# Synthesizer.net
KiCad netlist of a schematic drawn in Altium Designer
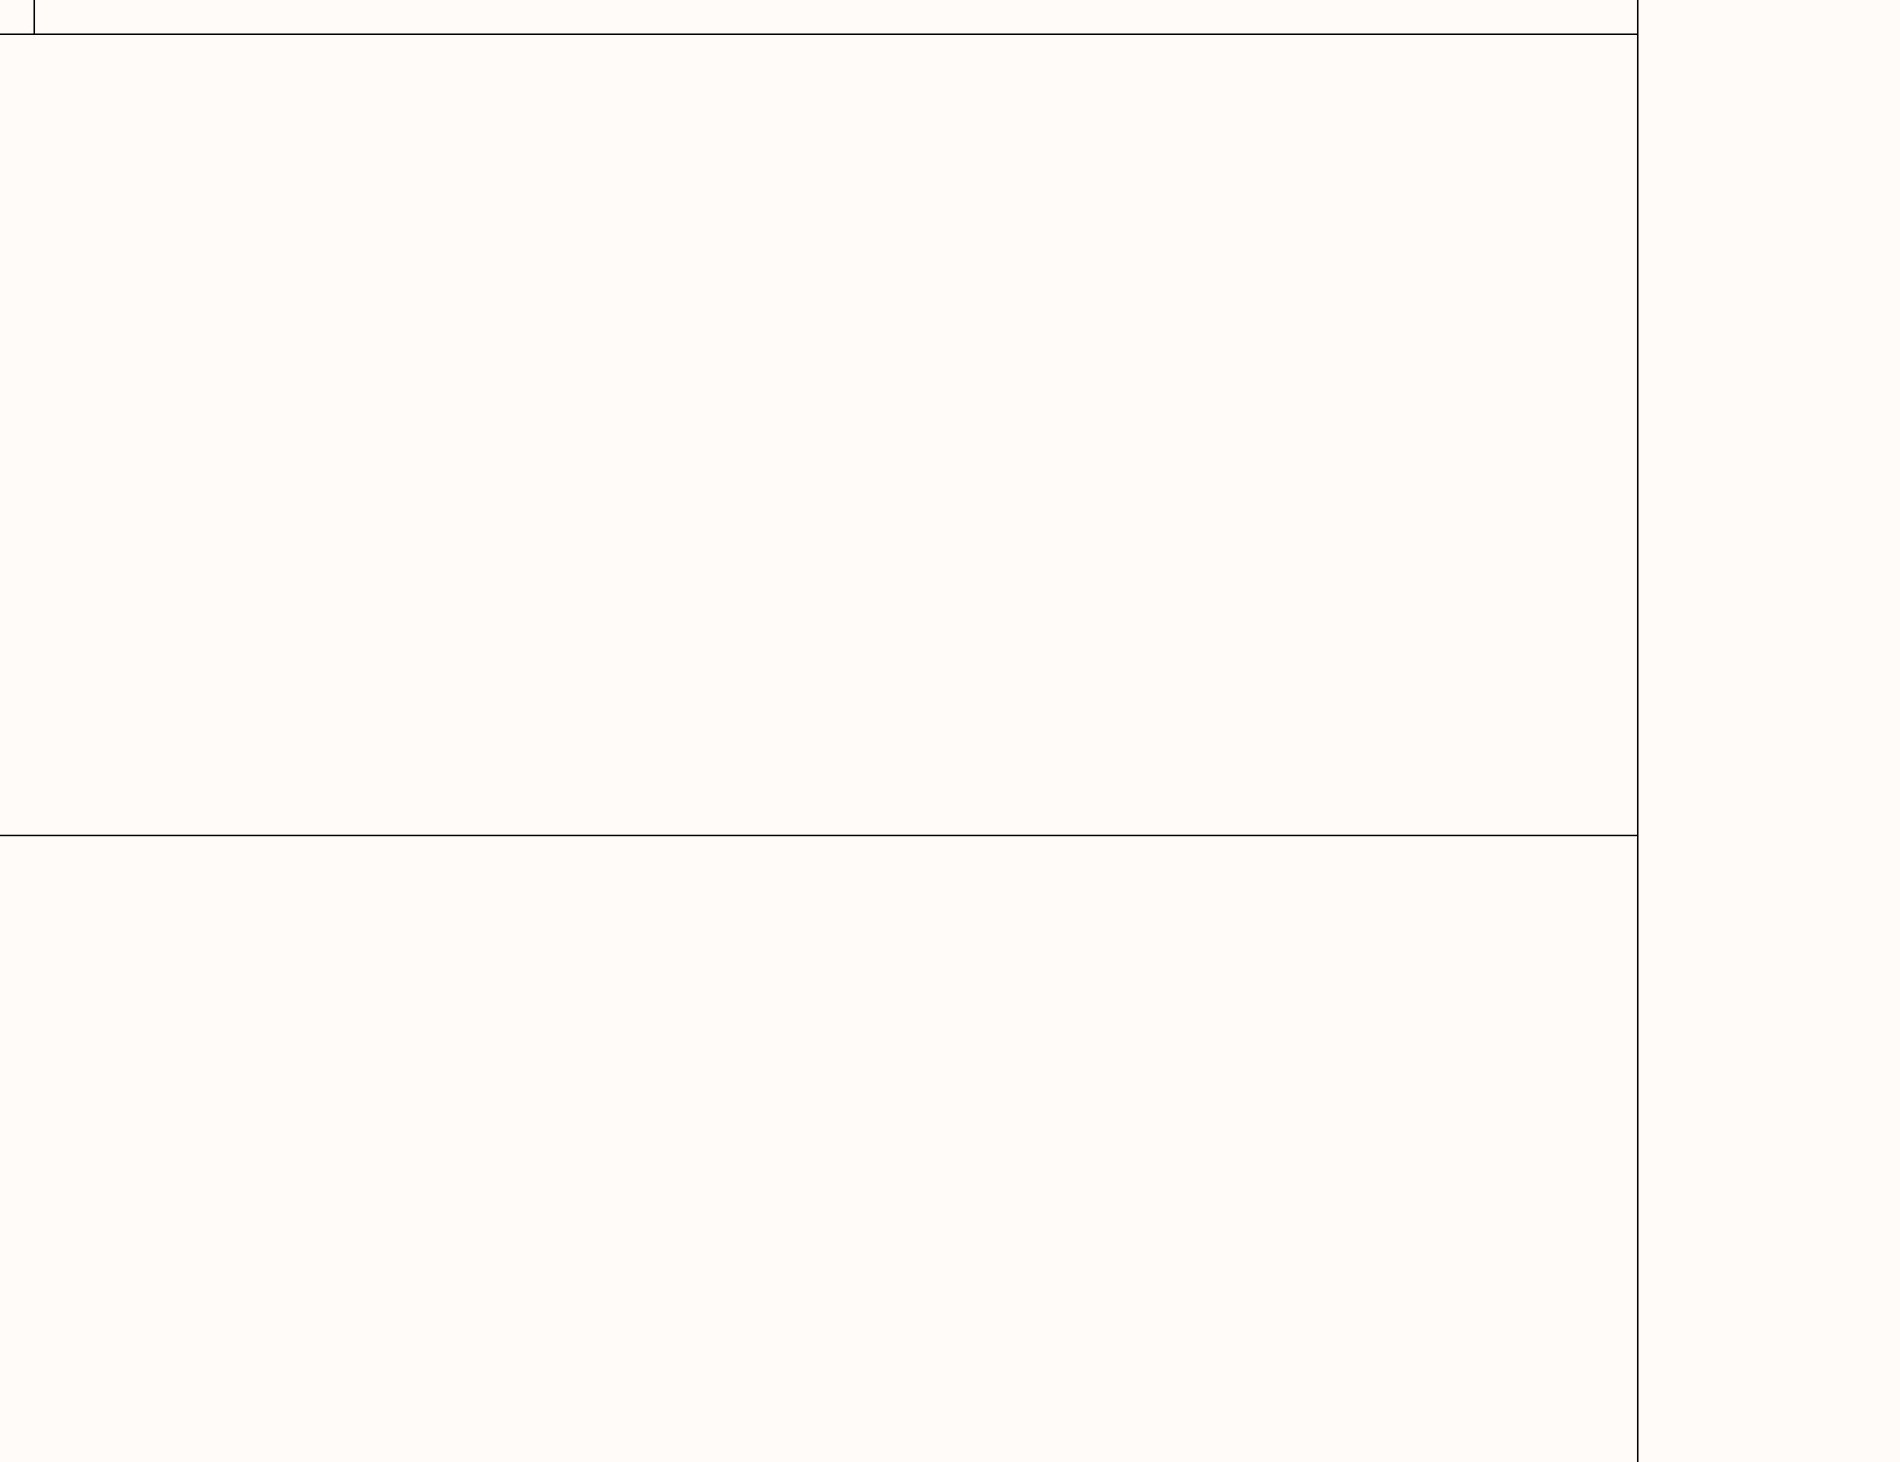
[diagram p0: Synthesizer.SchDoc, top column 1 of 4]
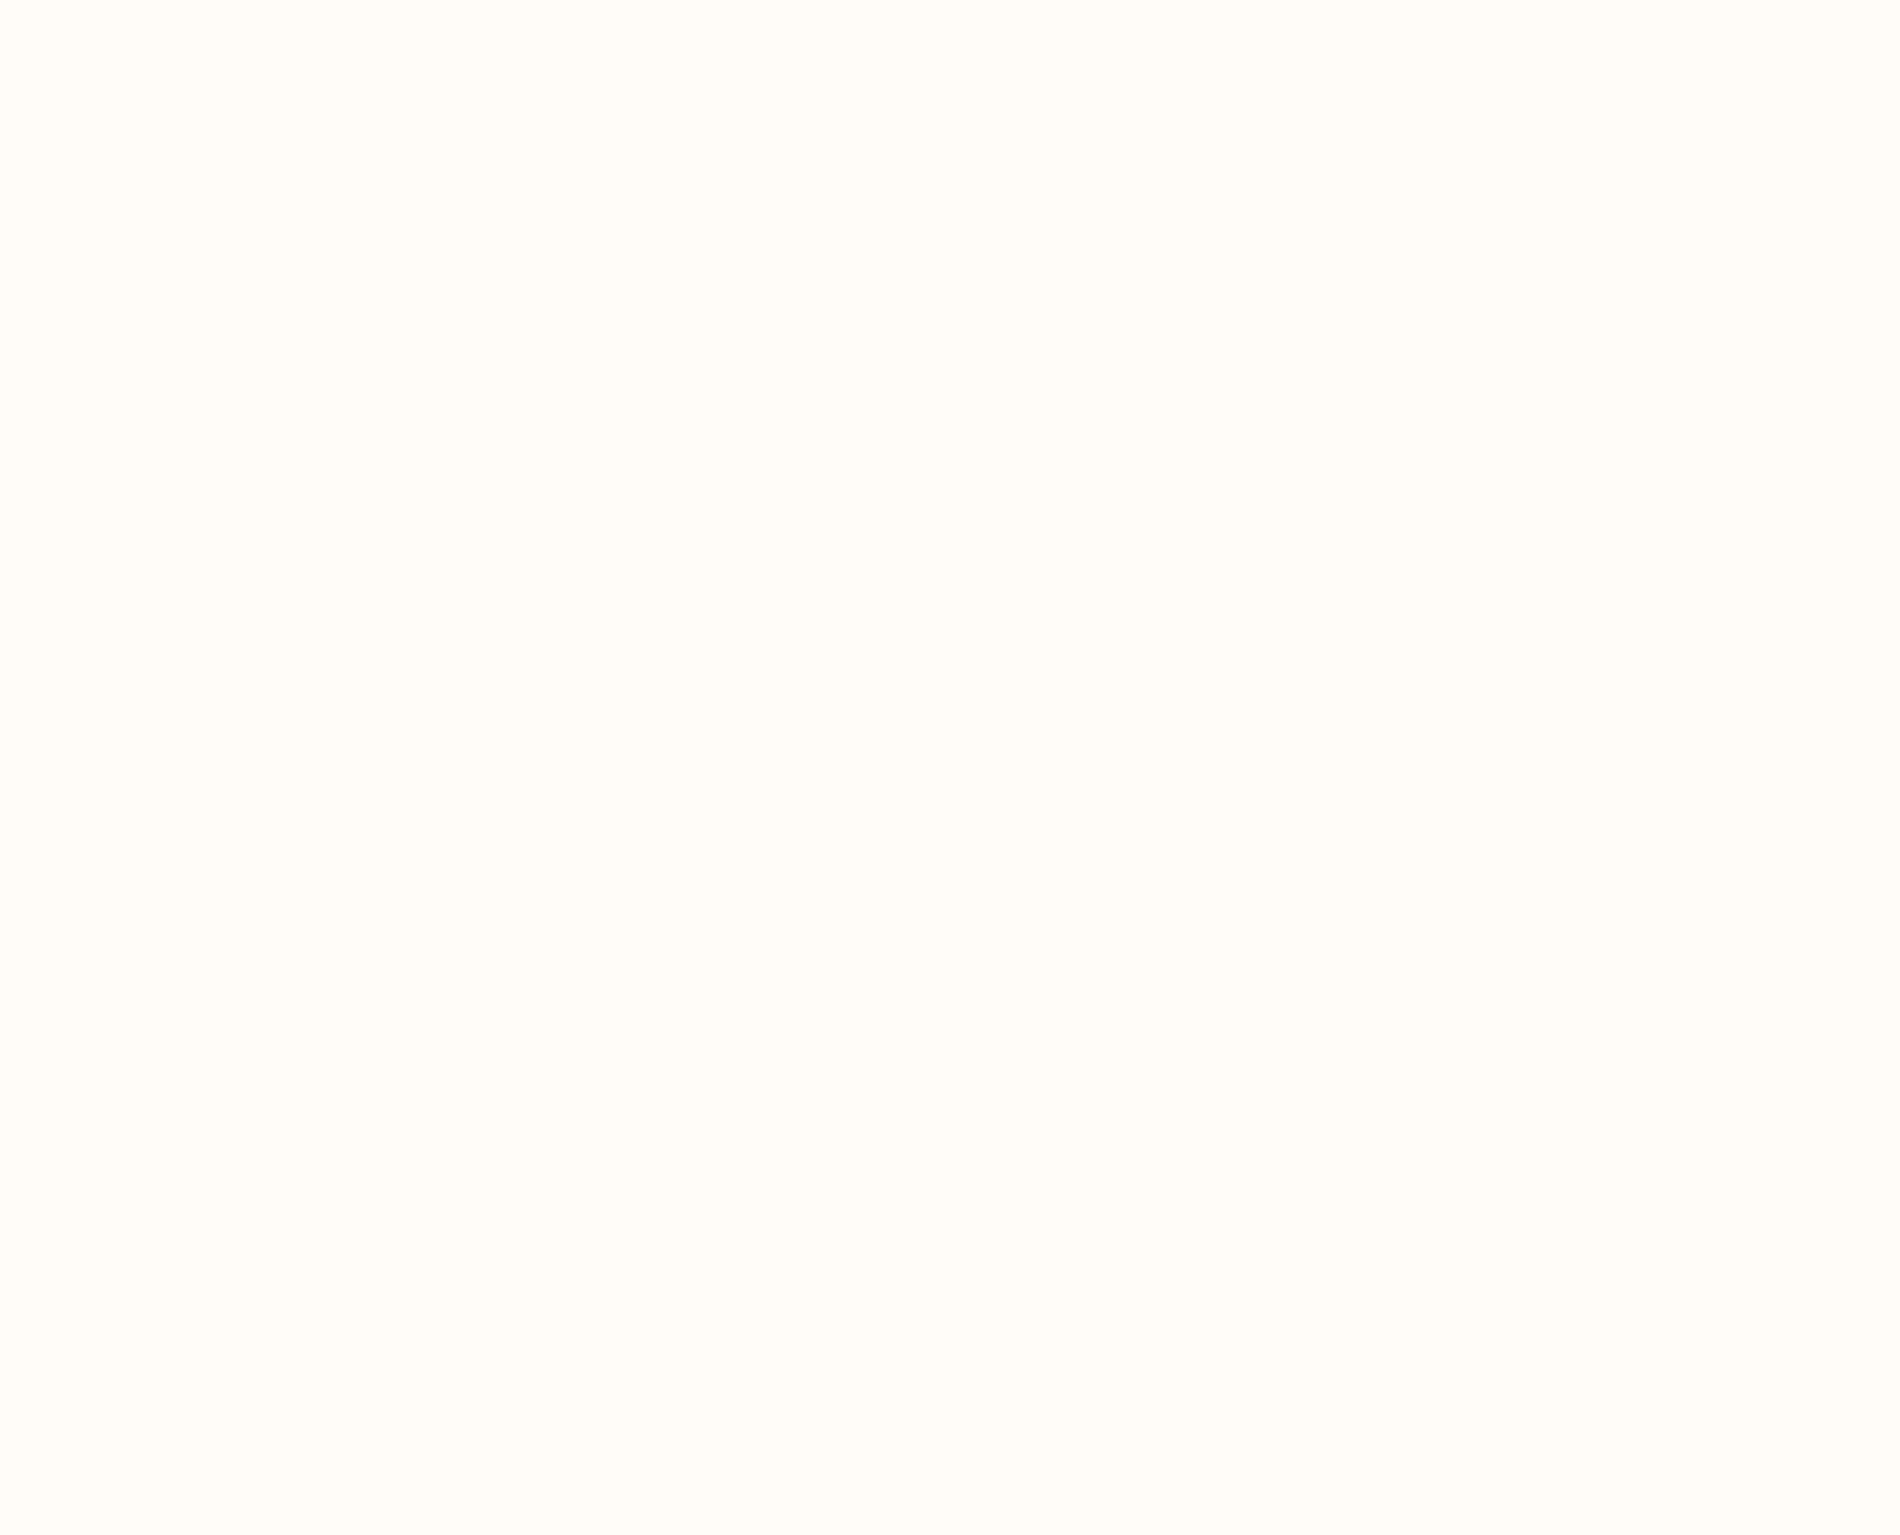
[diagram p1: Synthesizer.SchDoc, top column 2 of 4]
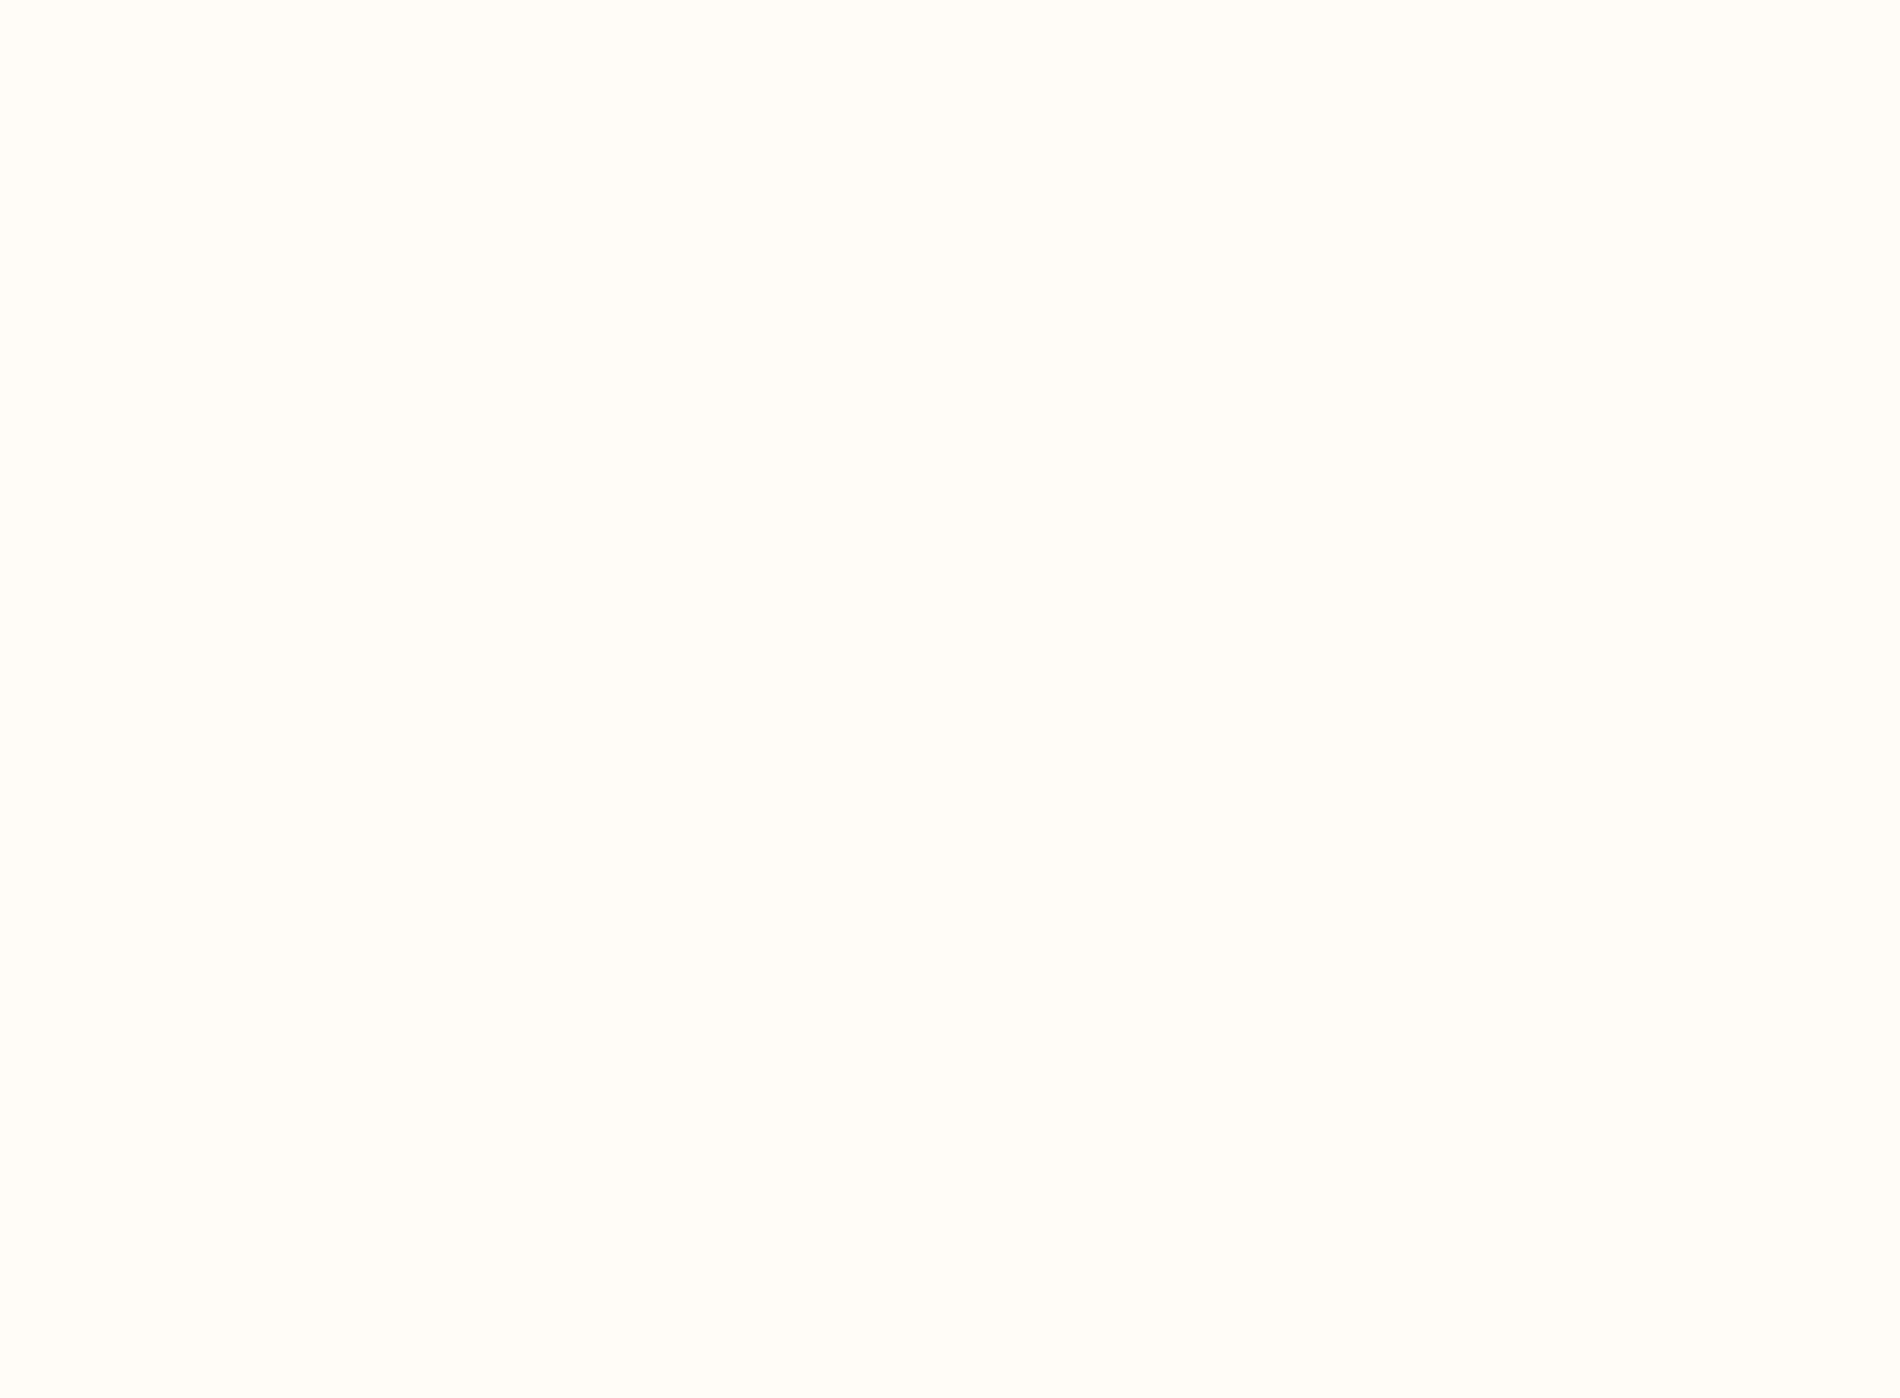
[diagram p2: Synthesizer.SchDoc, top column 3 of 4]
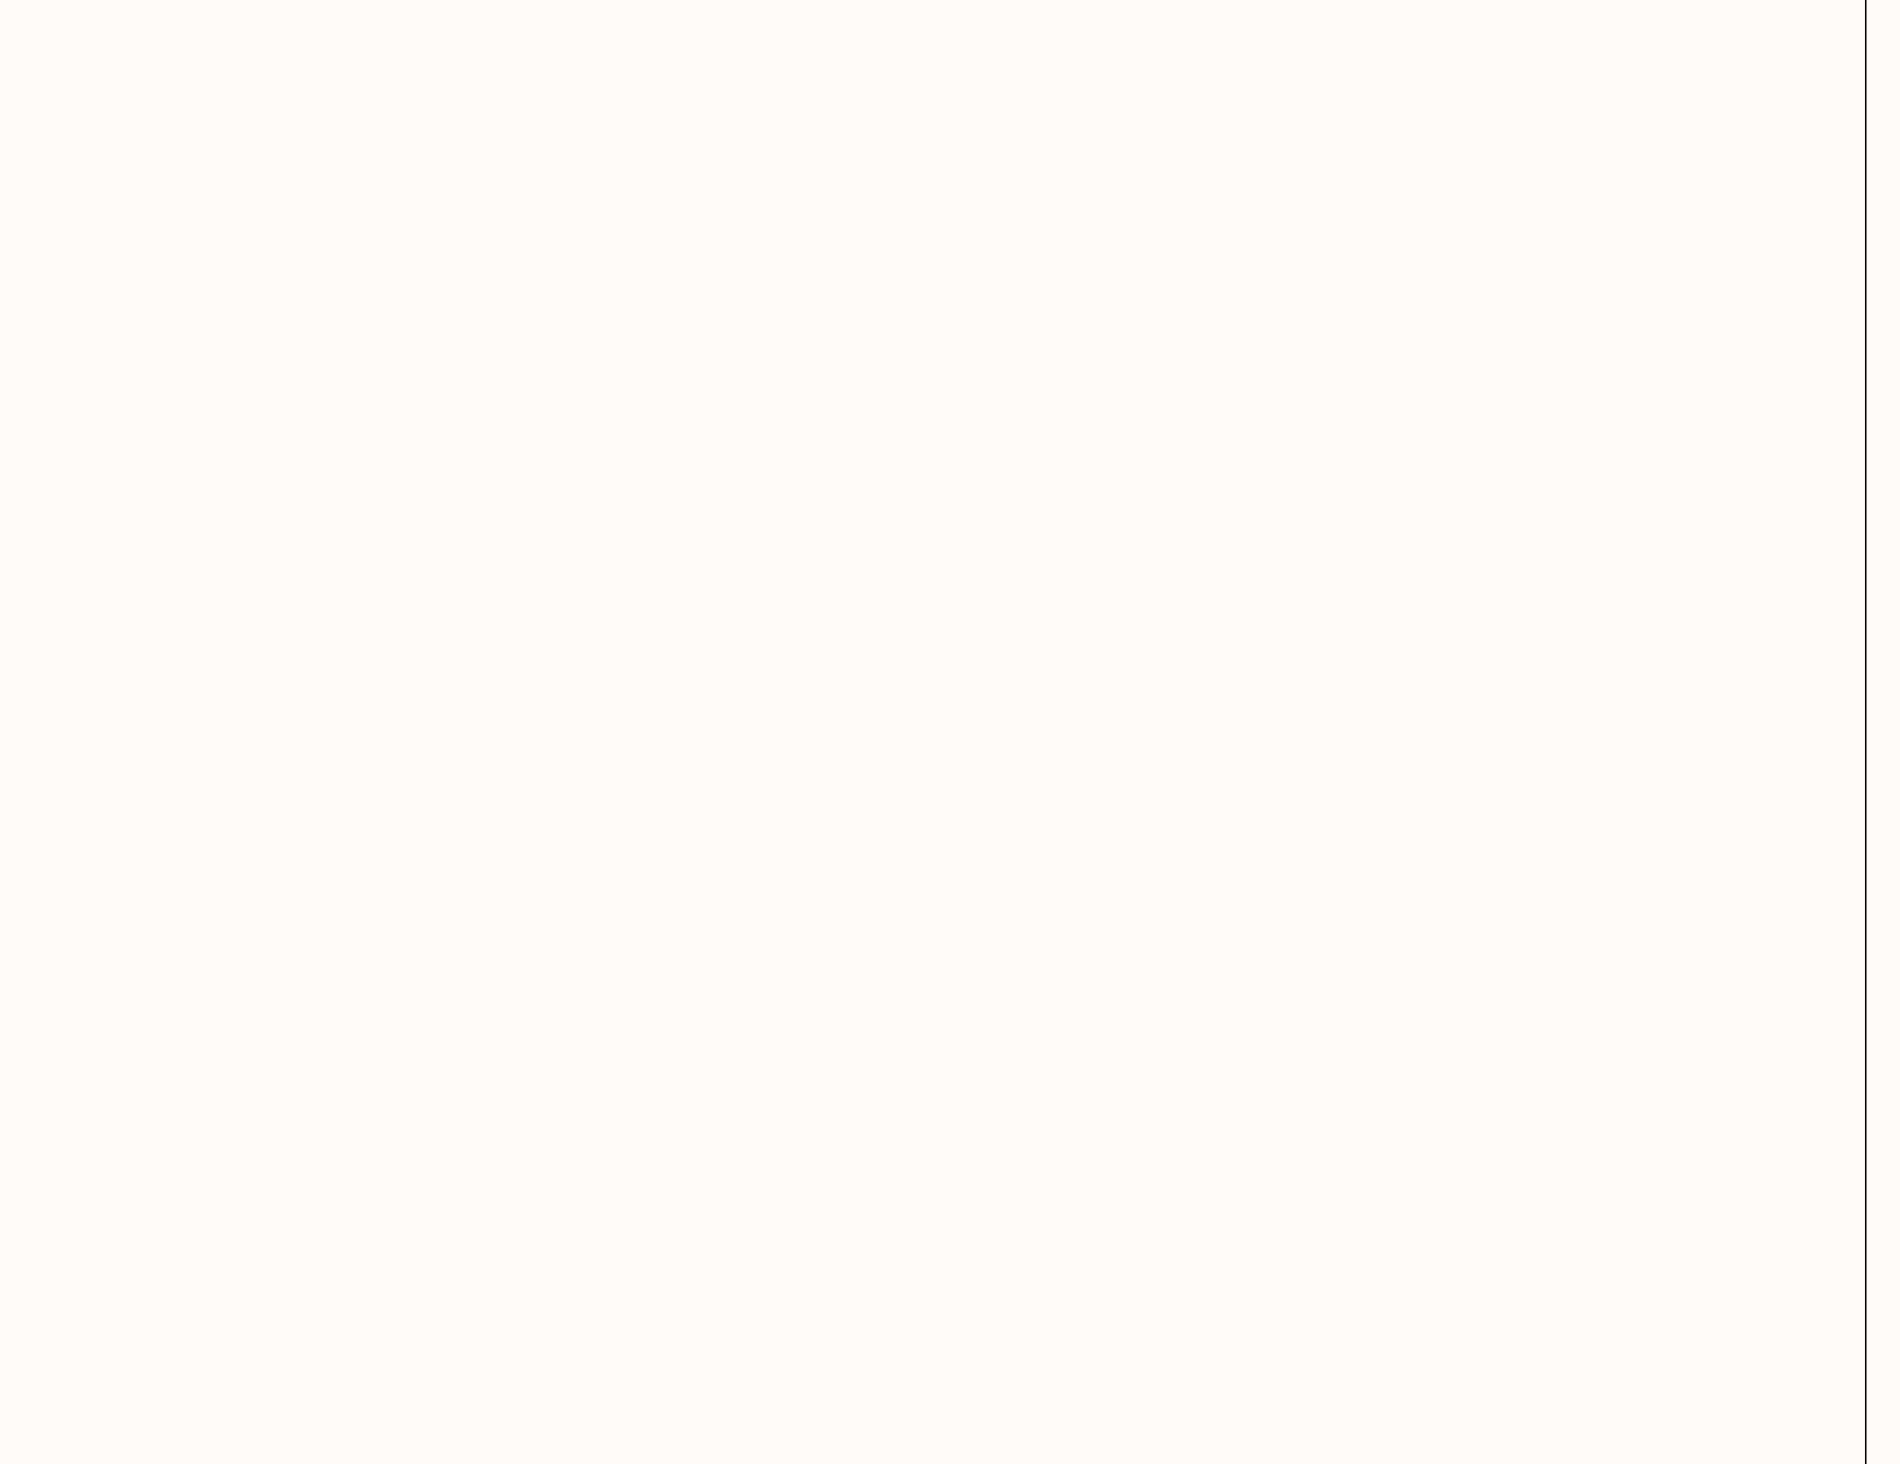
[diagram p3: Synthesizer.SchDoc, top column 4 of 4]
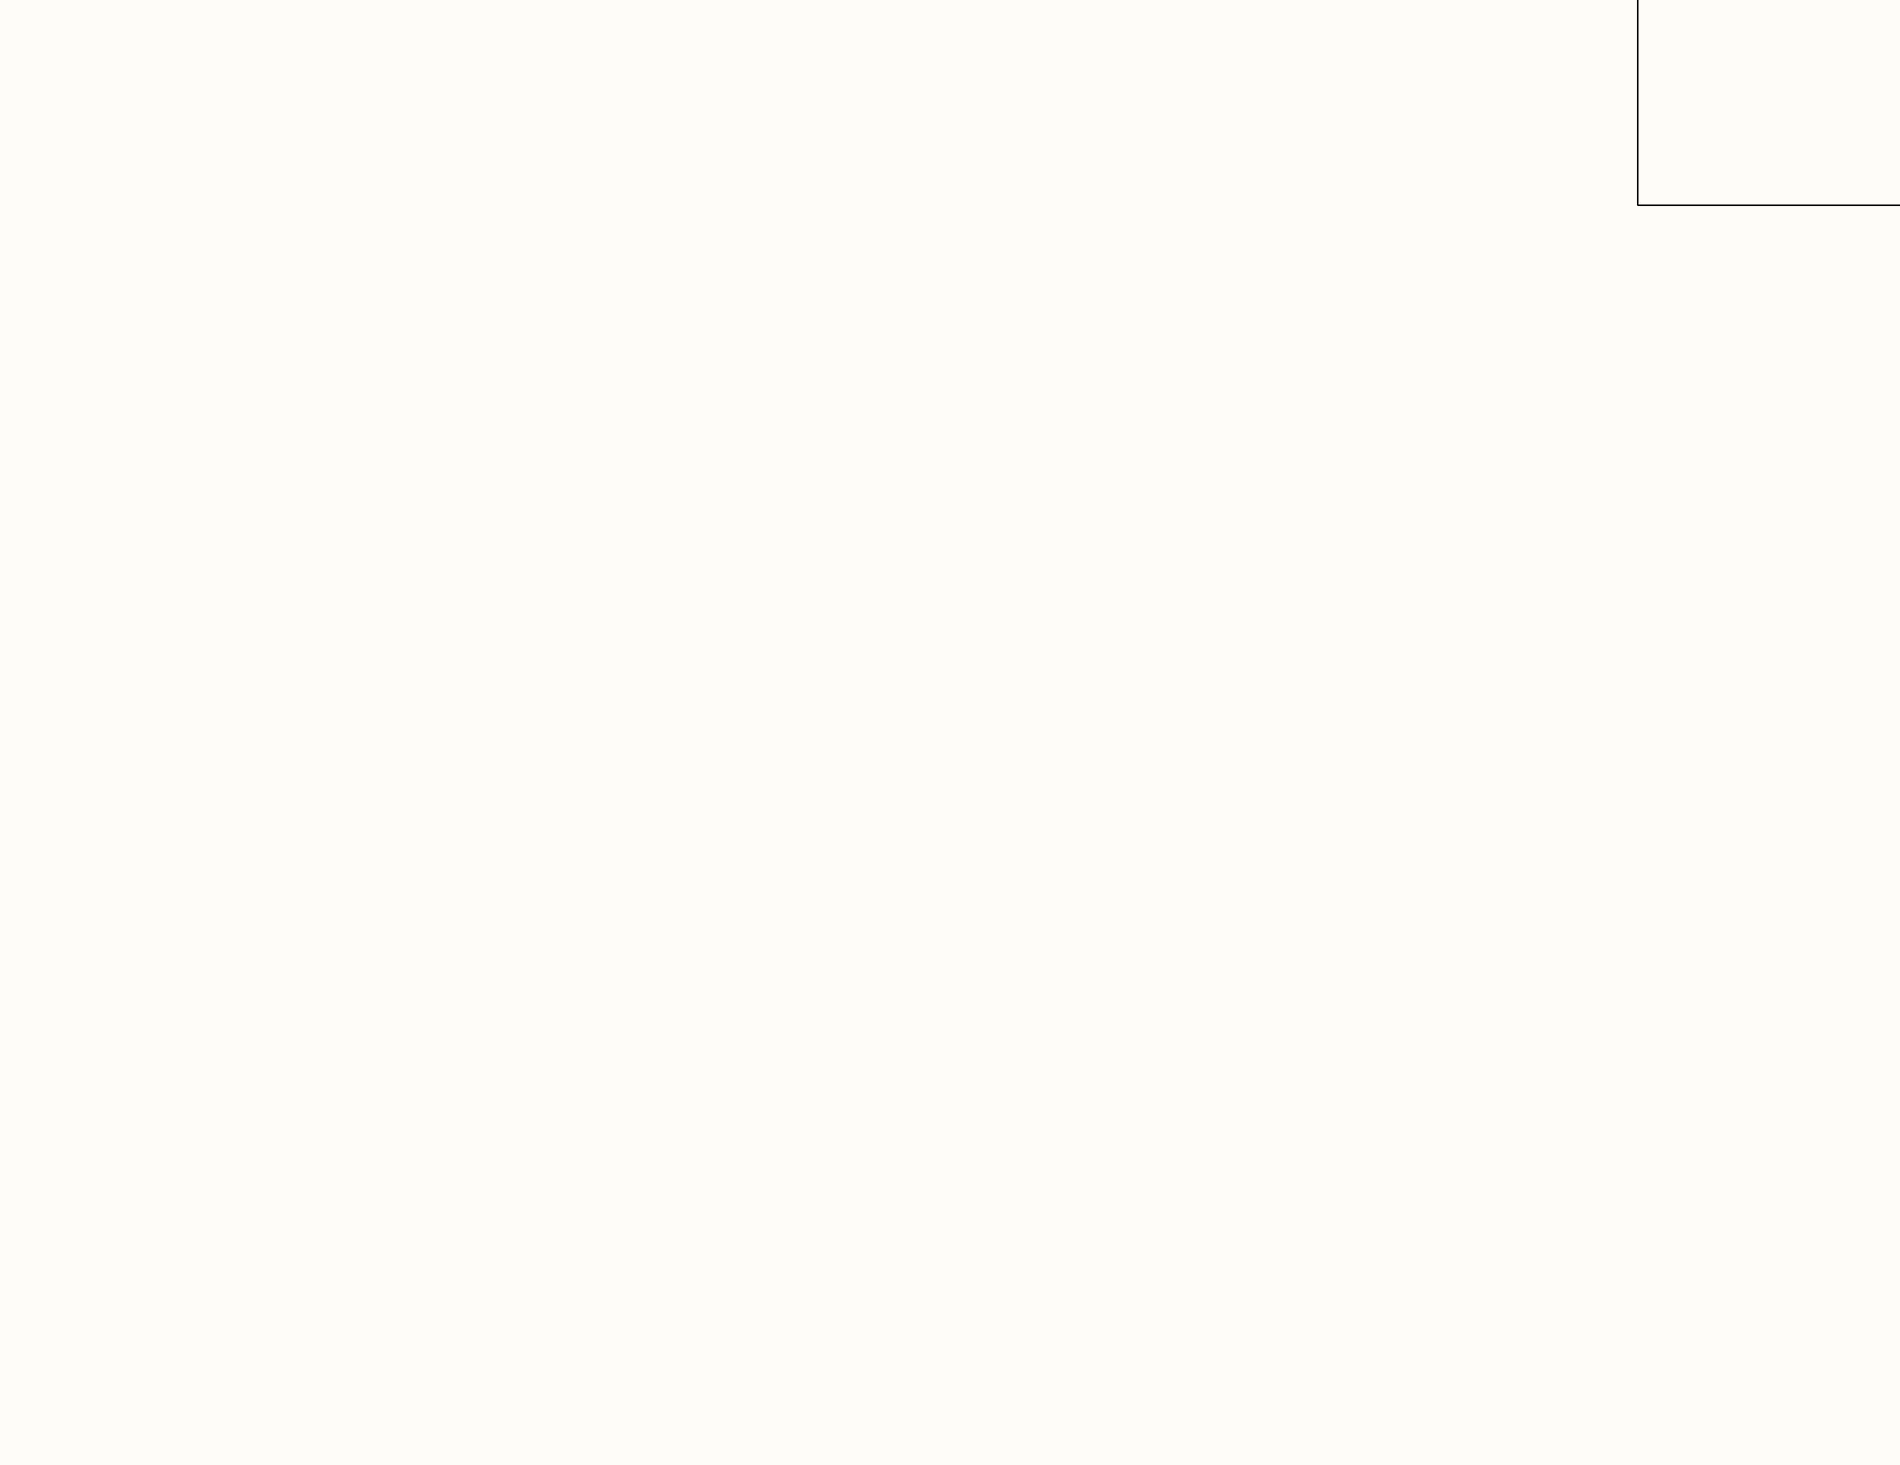
[diagram p4: Synthesizer.SchDoc, centre column 1 of 4]
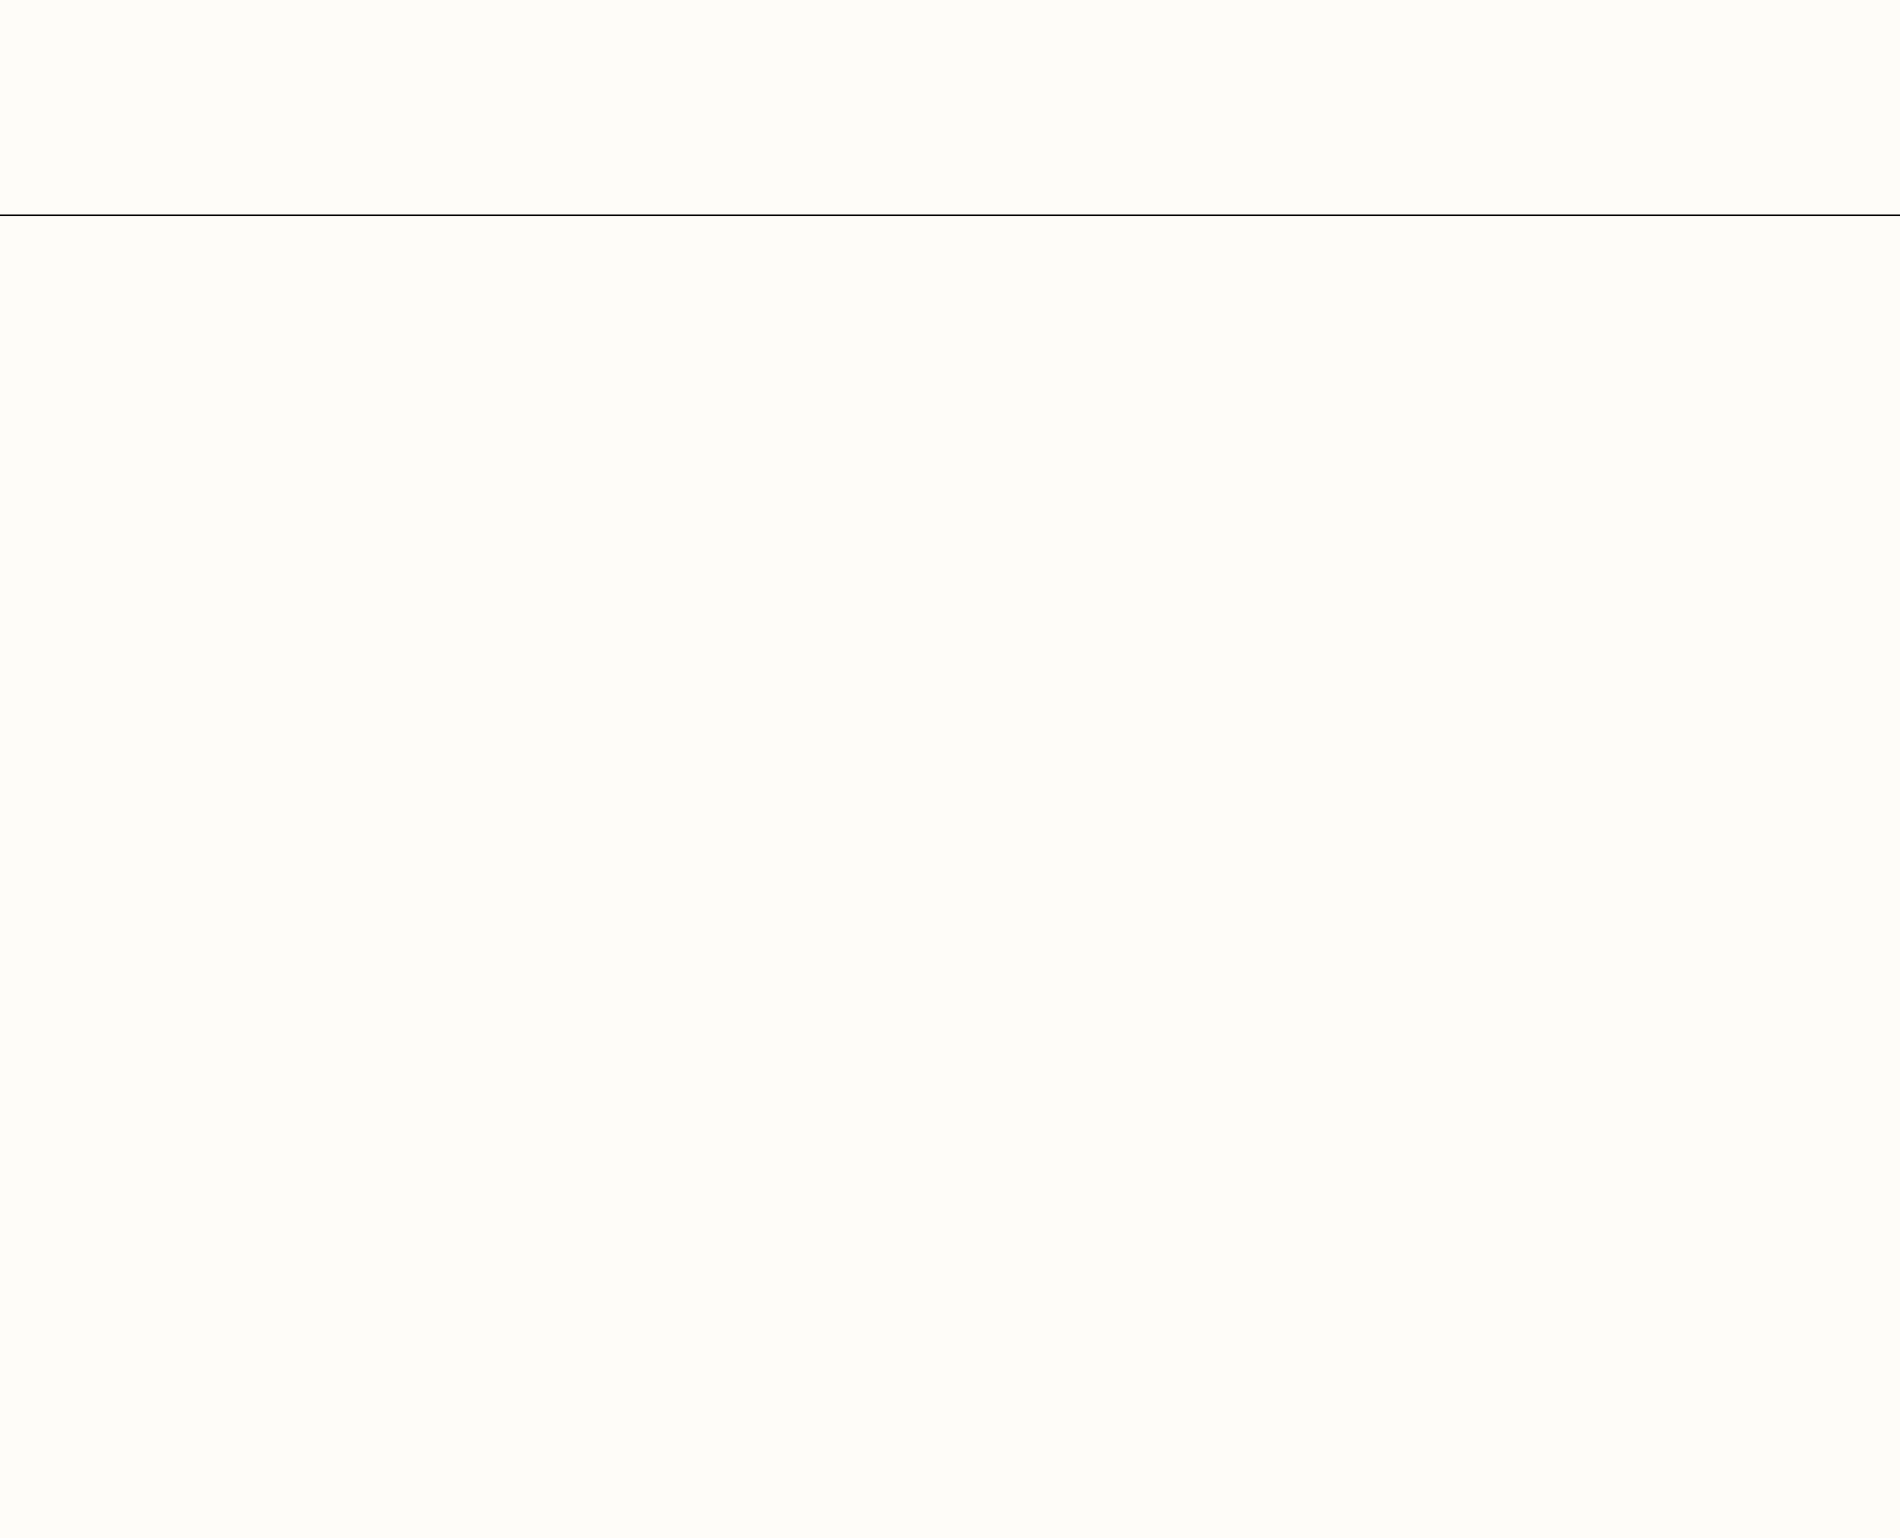
[diagram p5: Synthesizer.SchDoc, centre column 2 of 4]
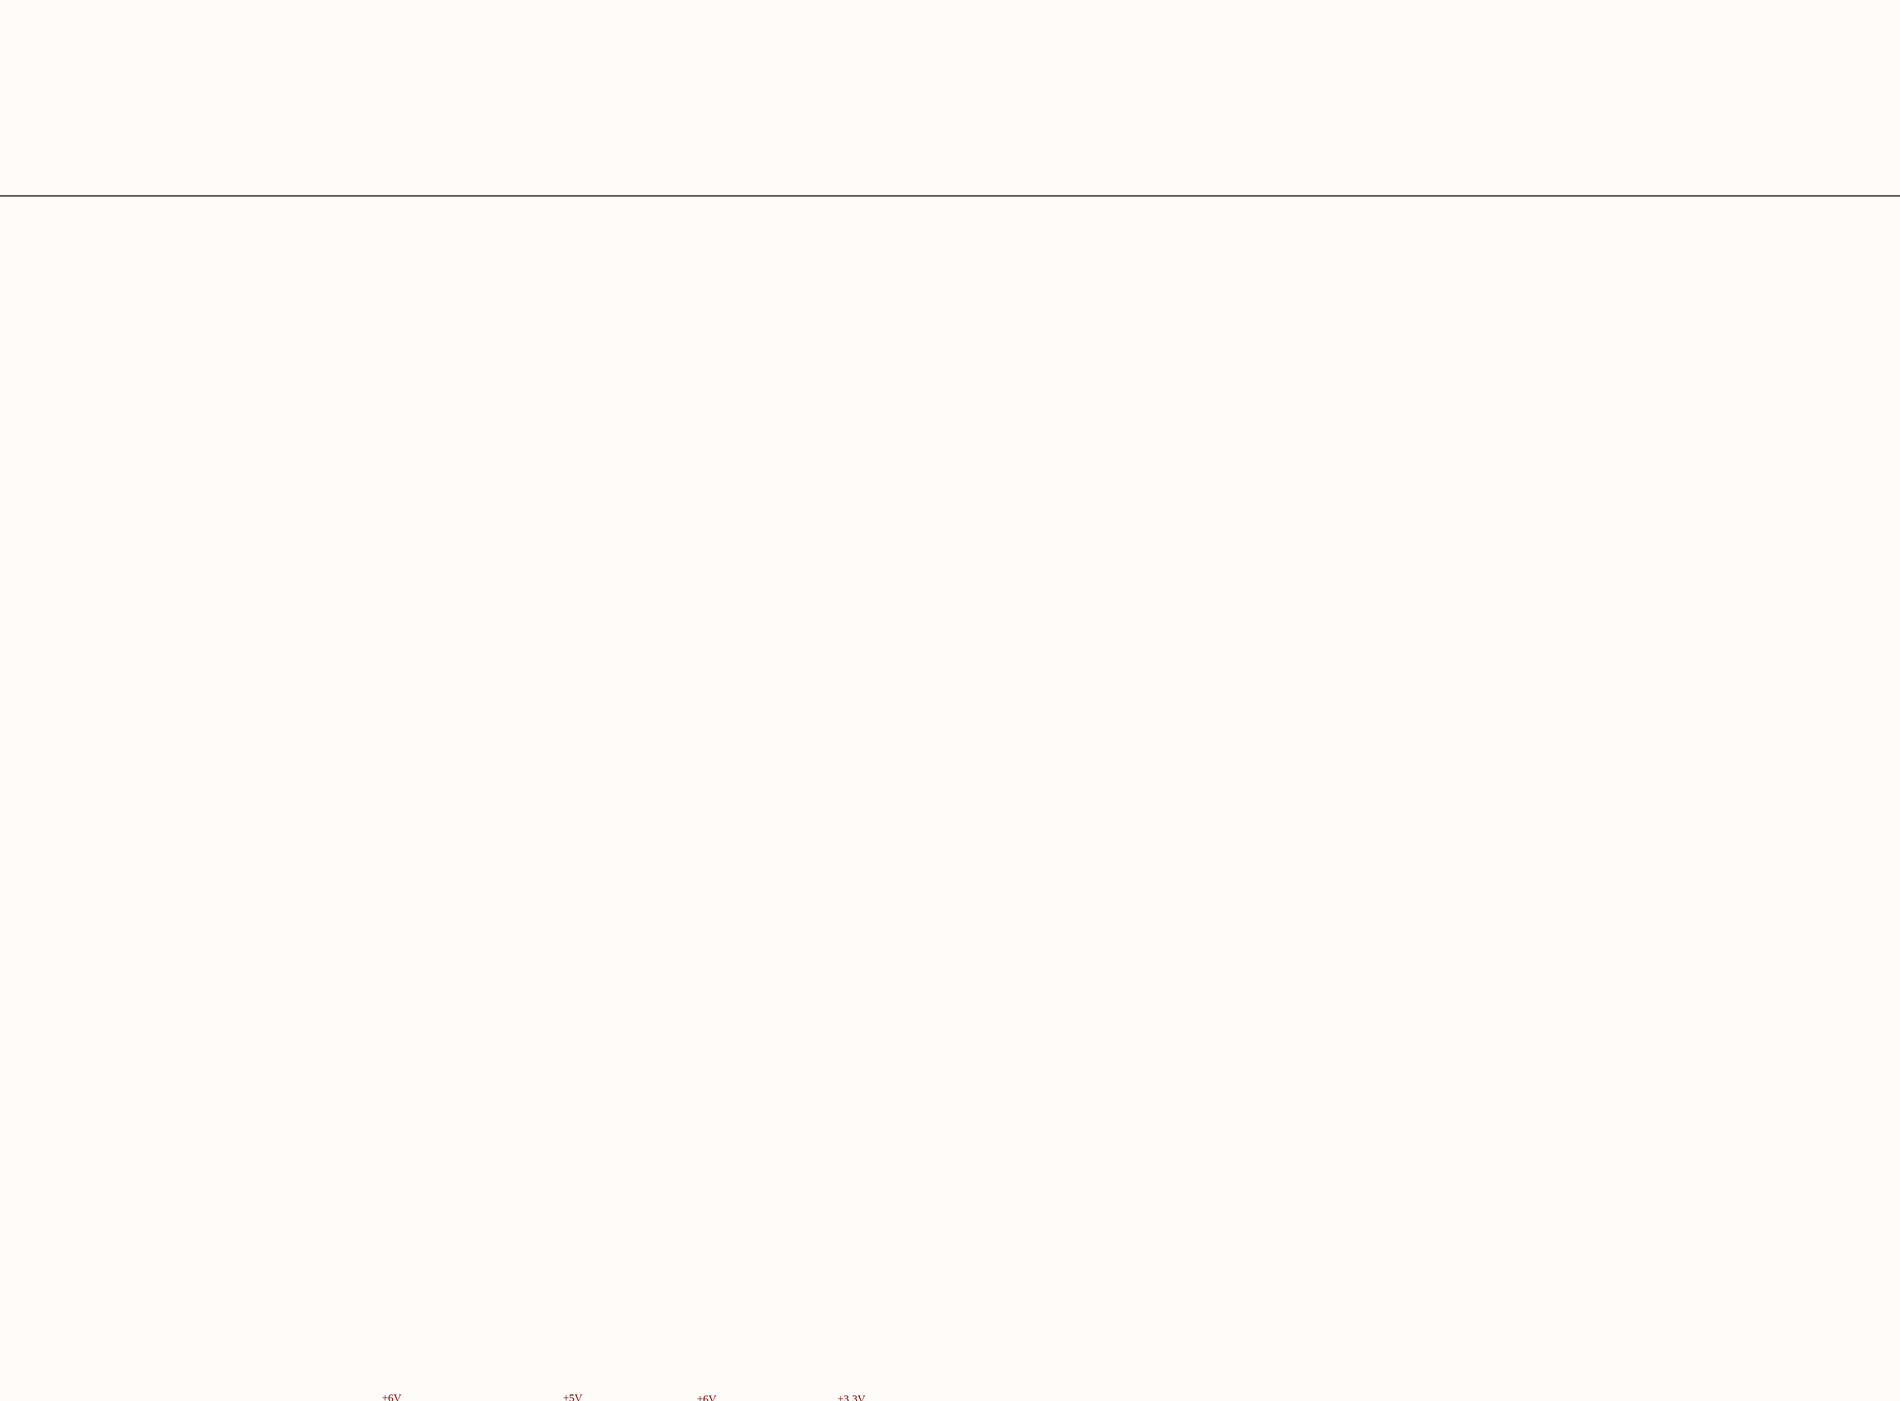
[diagram p6: Synthesizer.SchDoc, centre column 3 of 4]
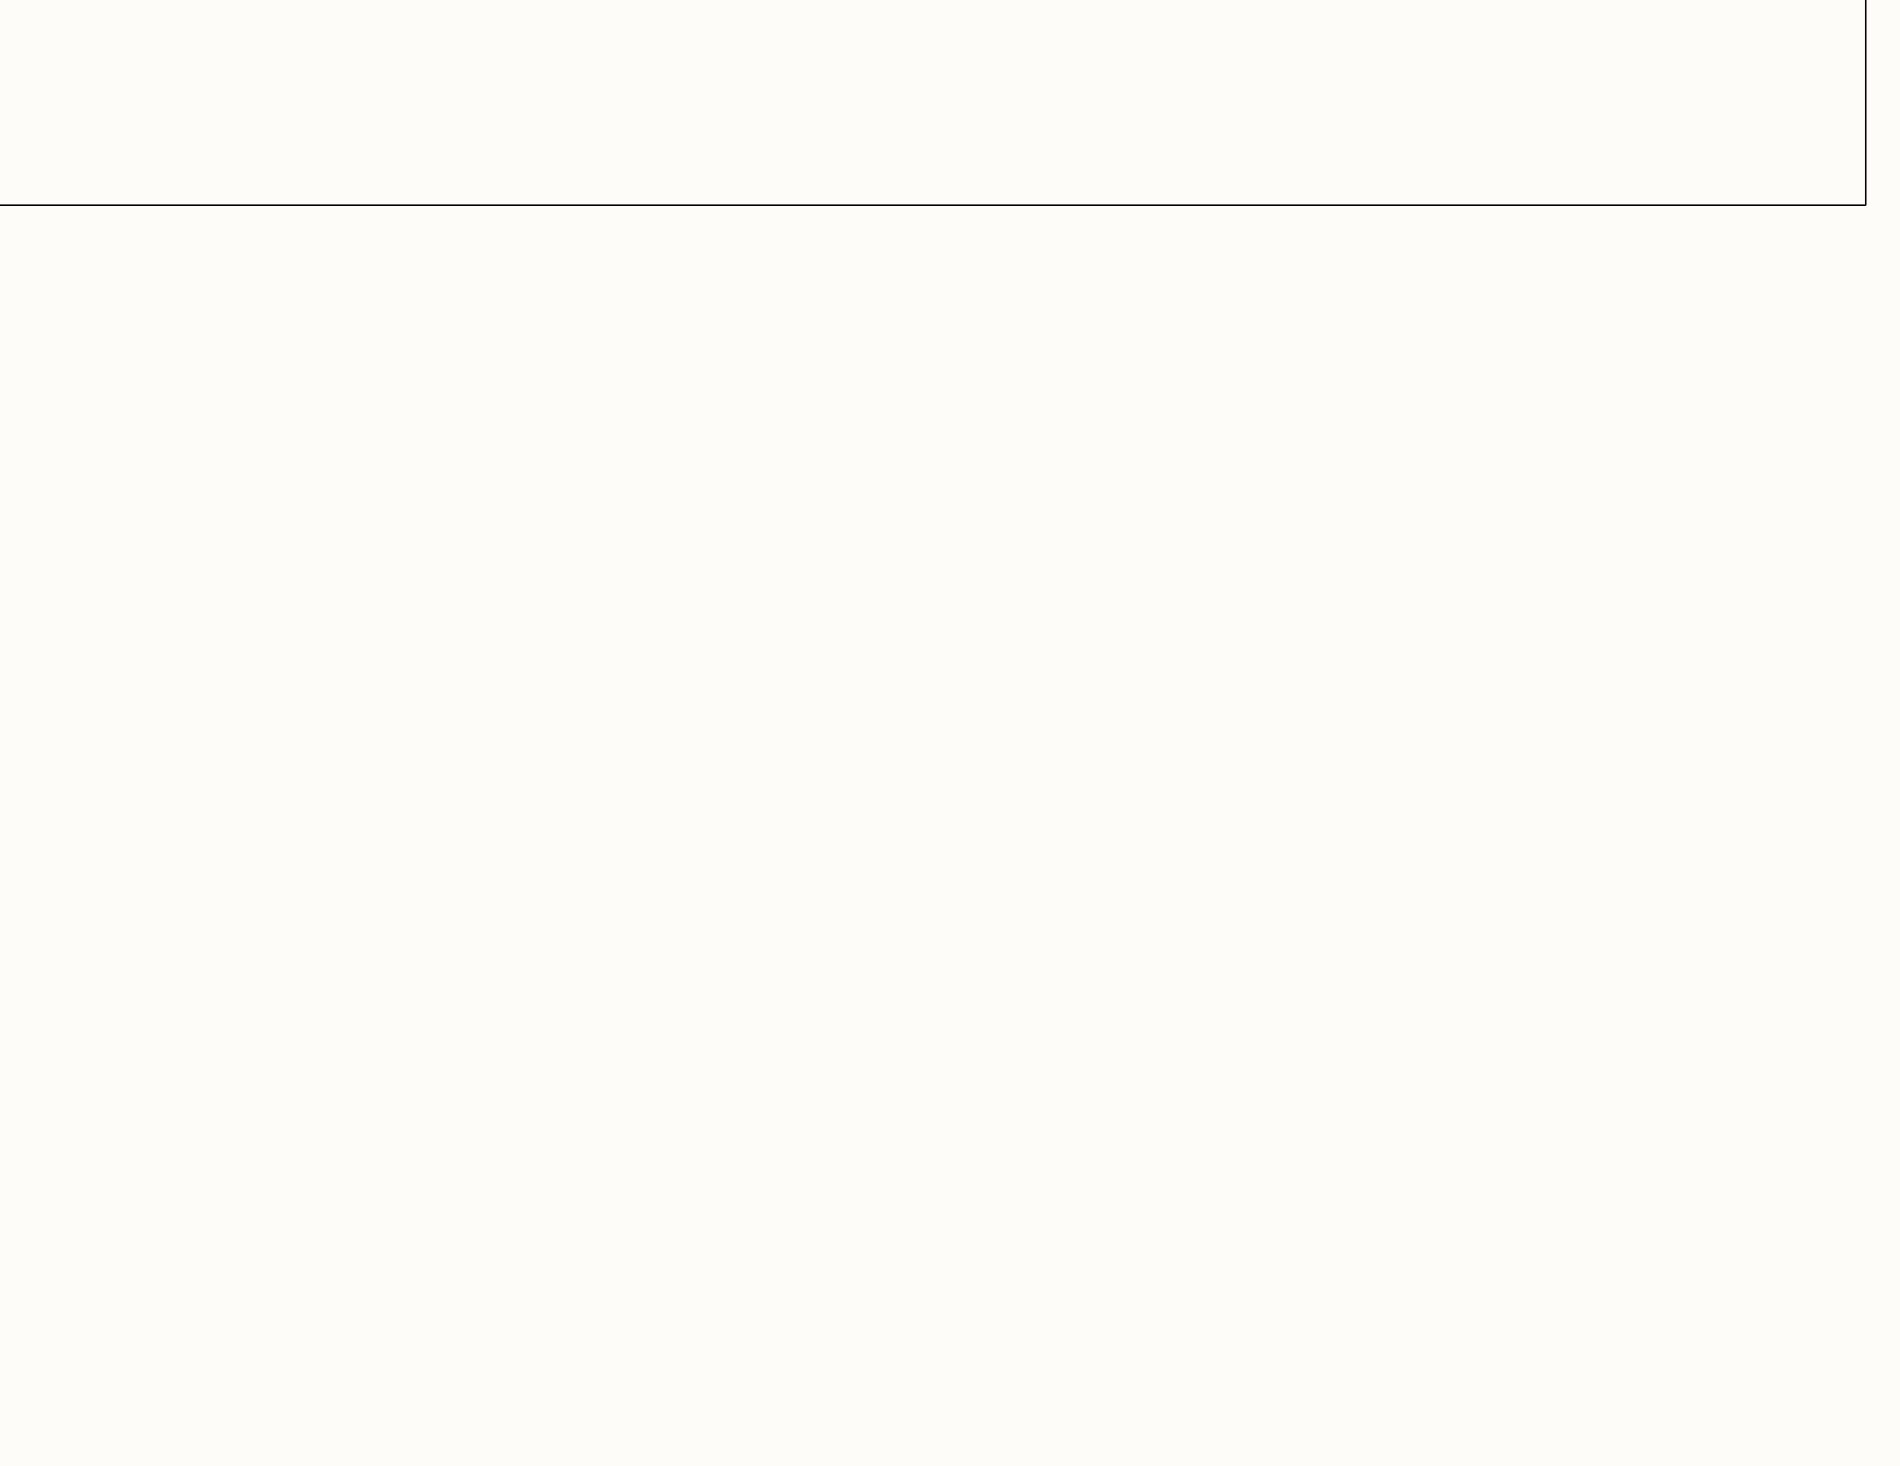
[diagram p7: Synthesizer.SchDoc, centre column 4 of 4]
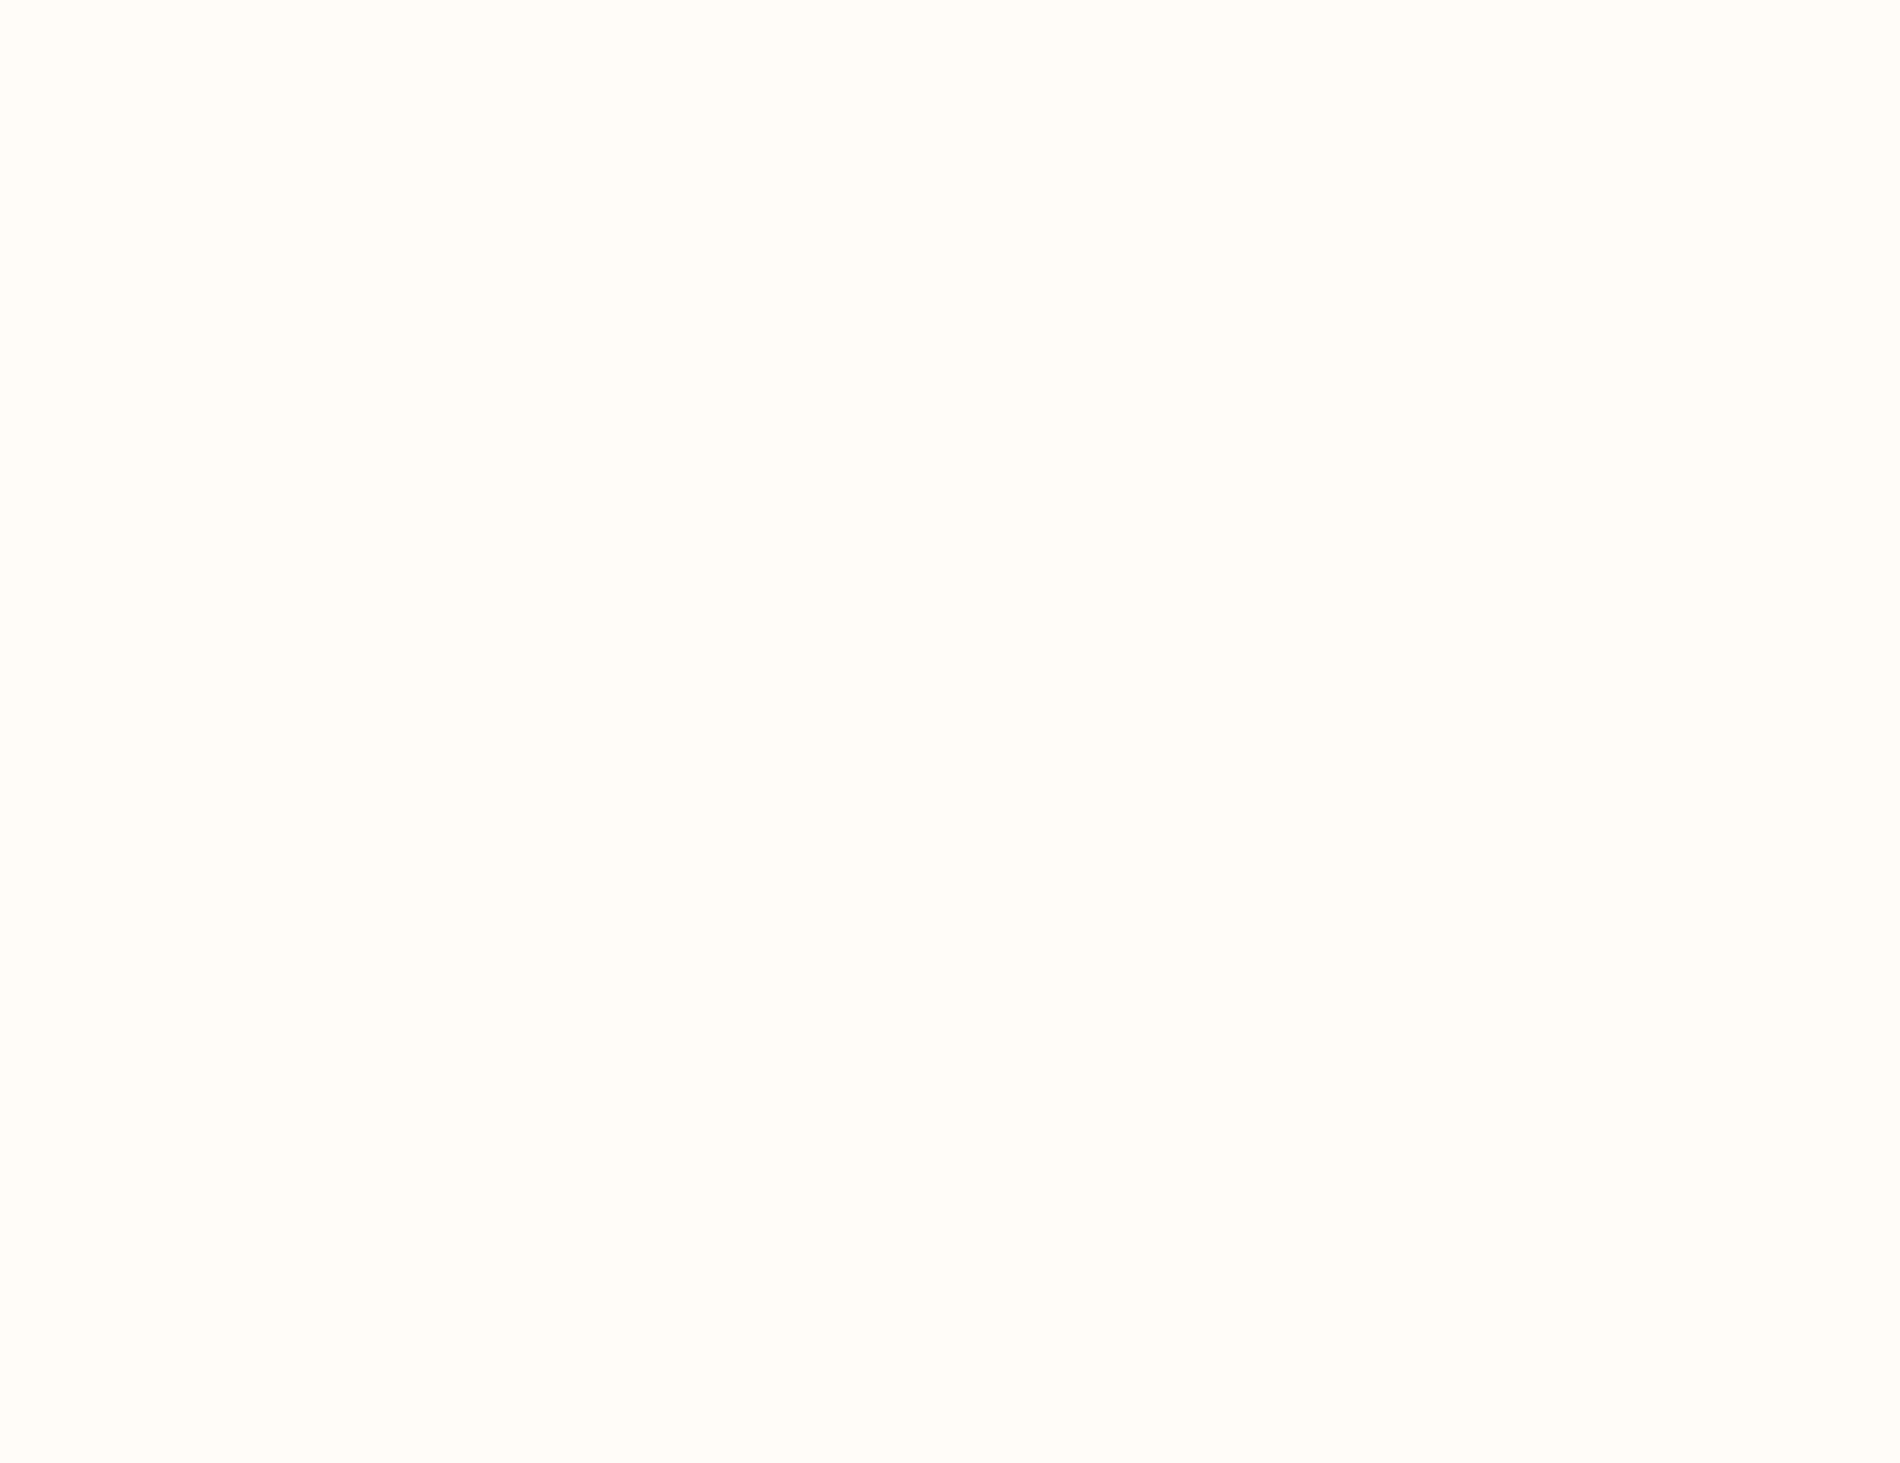
[diagram p8: Synthesizer.SchDoc, bottom column 1 of 4]
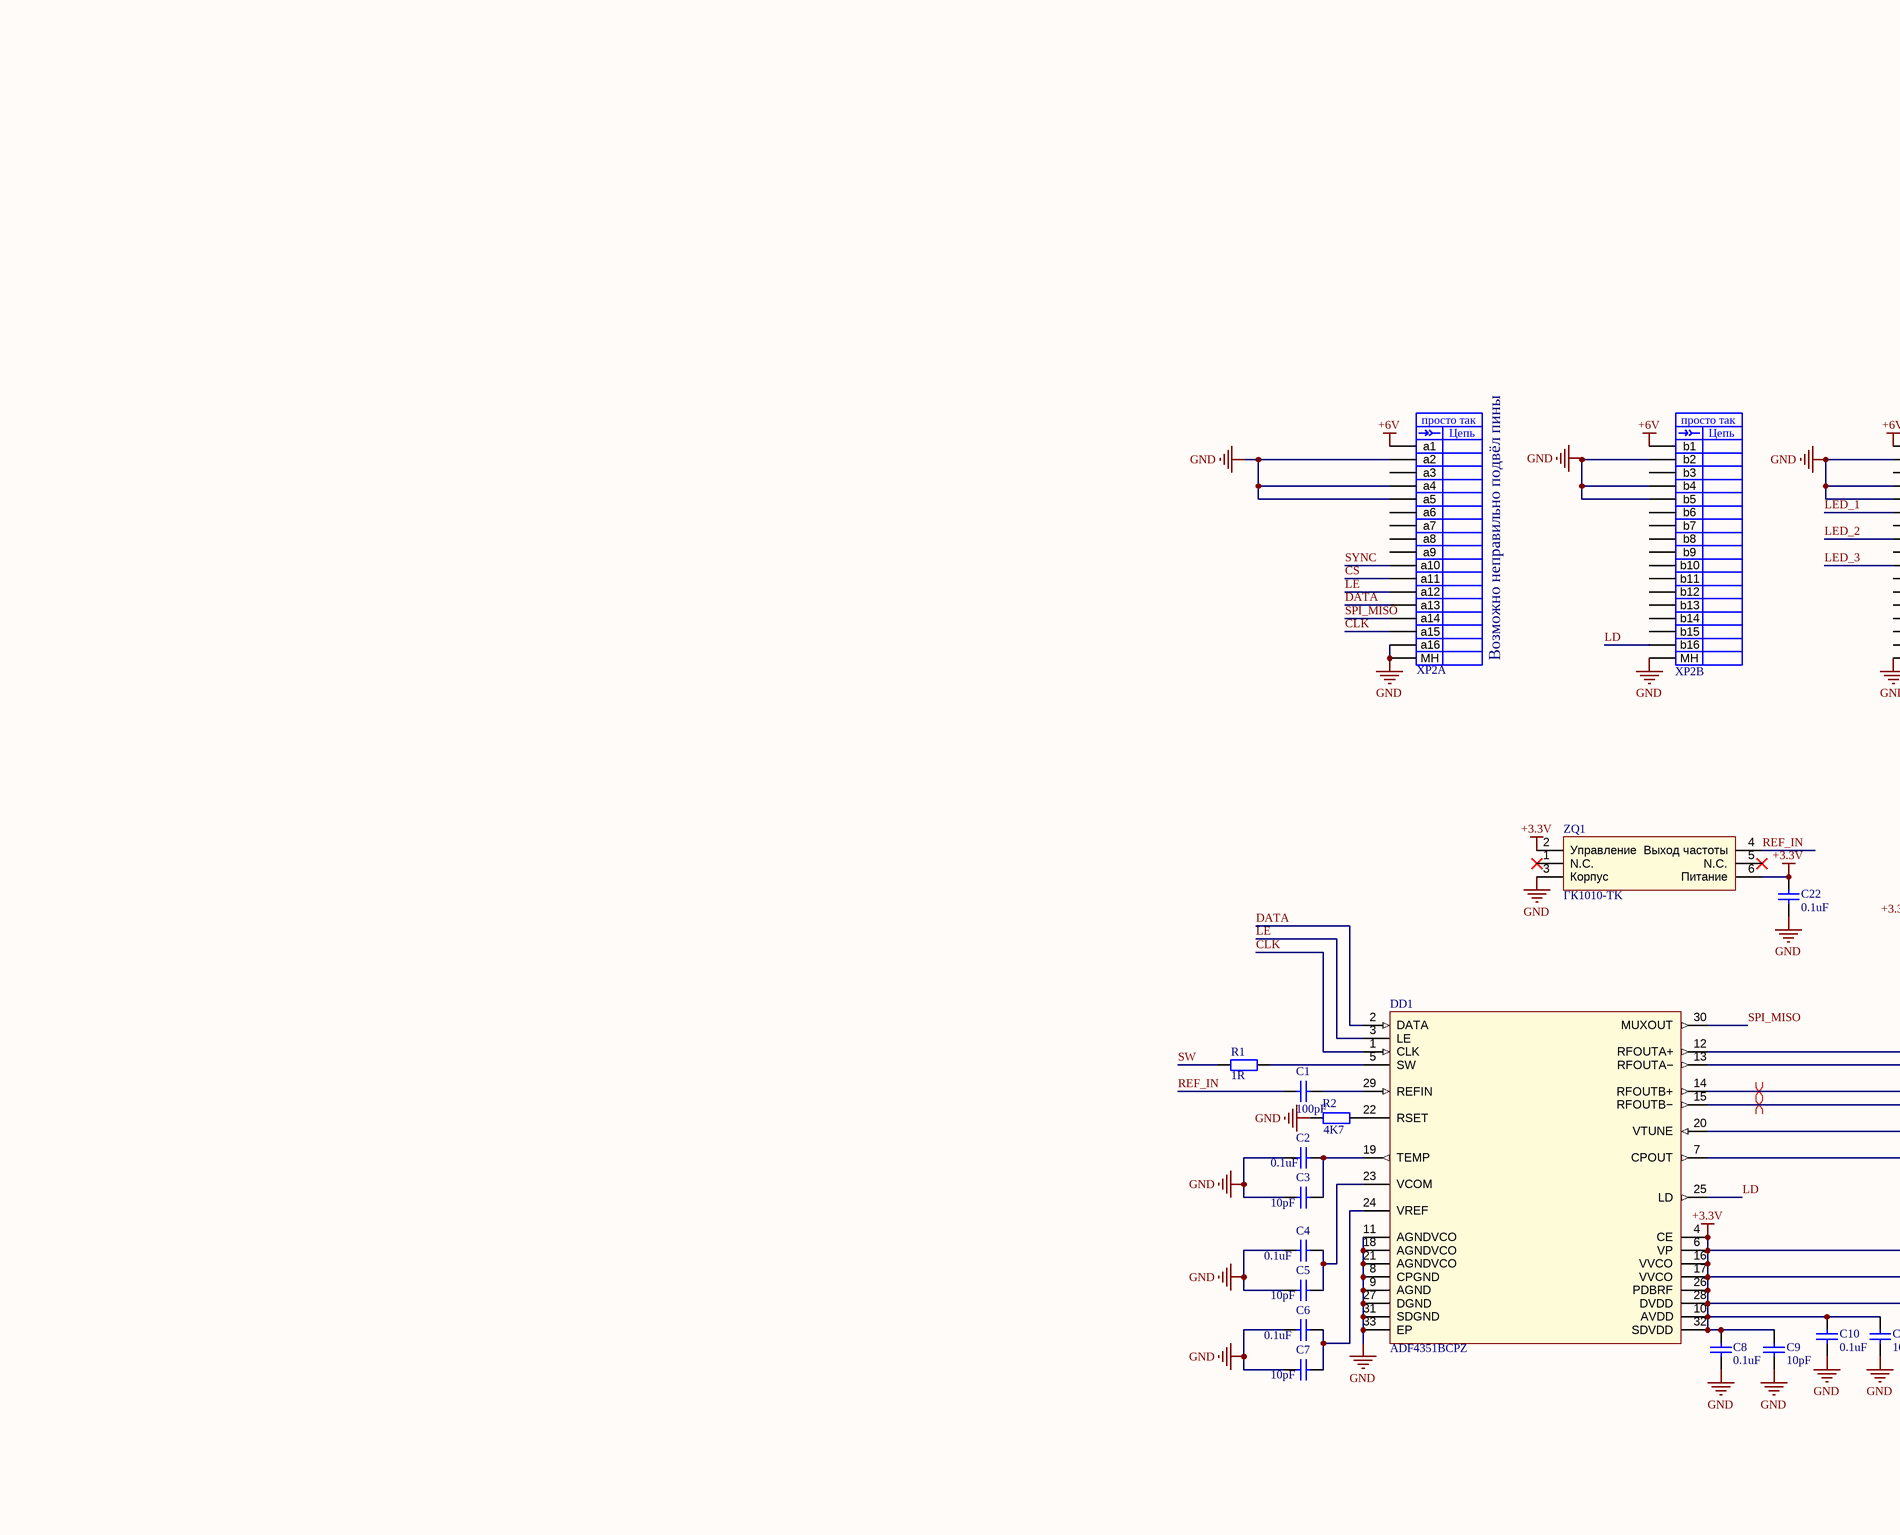
[diagram p9: Synthesizer.SchDoc, bottom column 2 of 4]
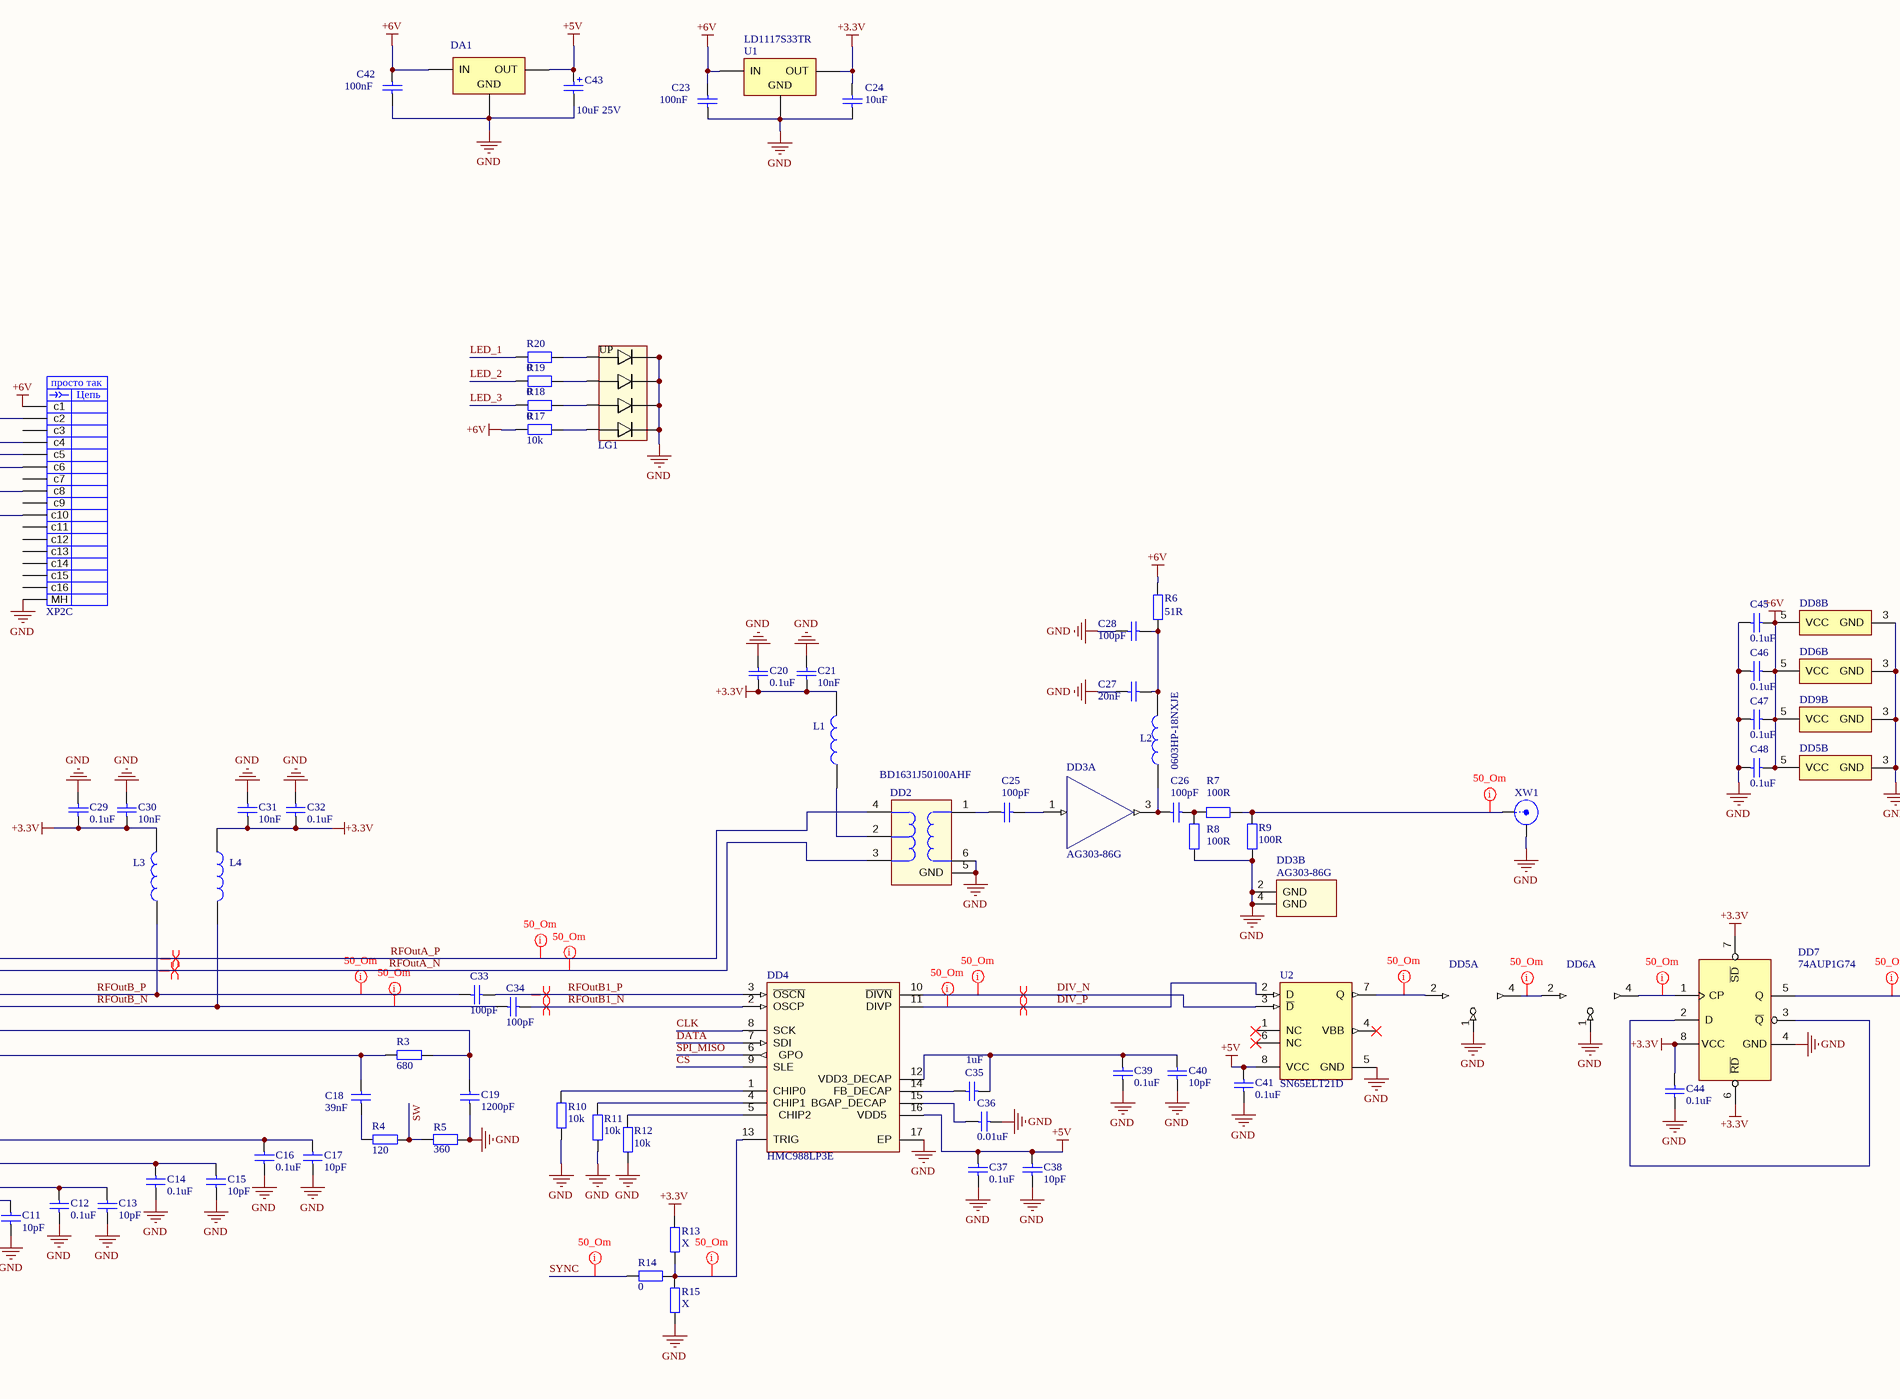
[diagram p10: Synthesizer.SchDoc, bottom column 3 of 4]
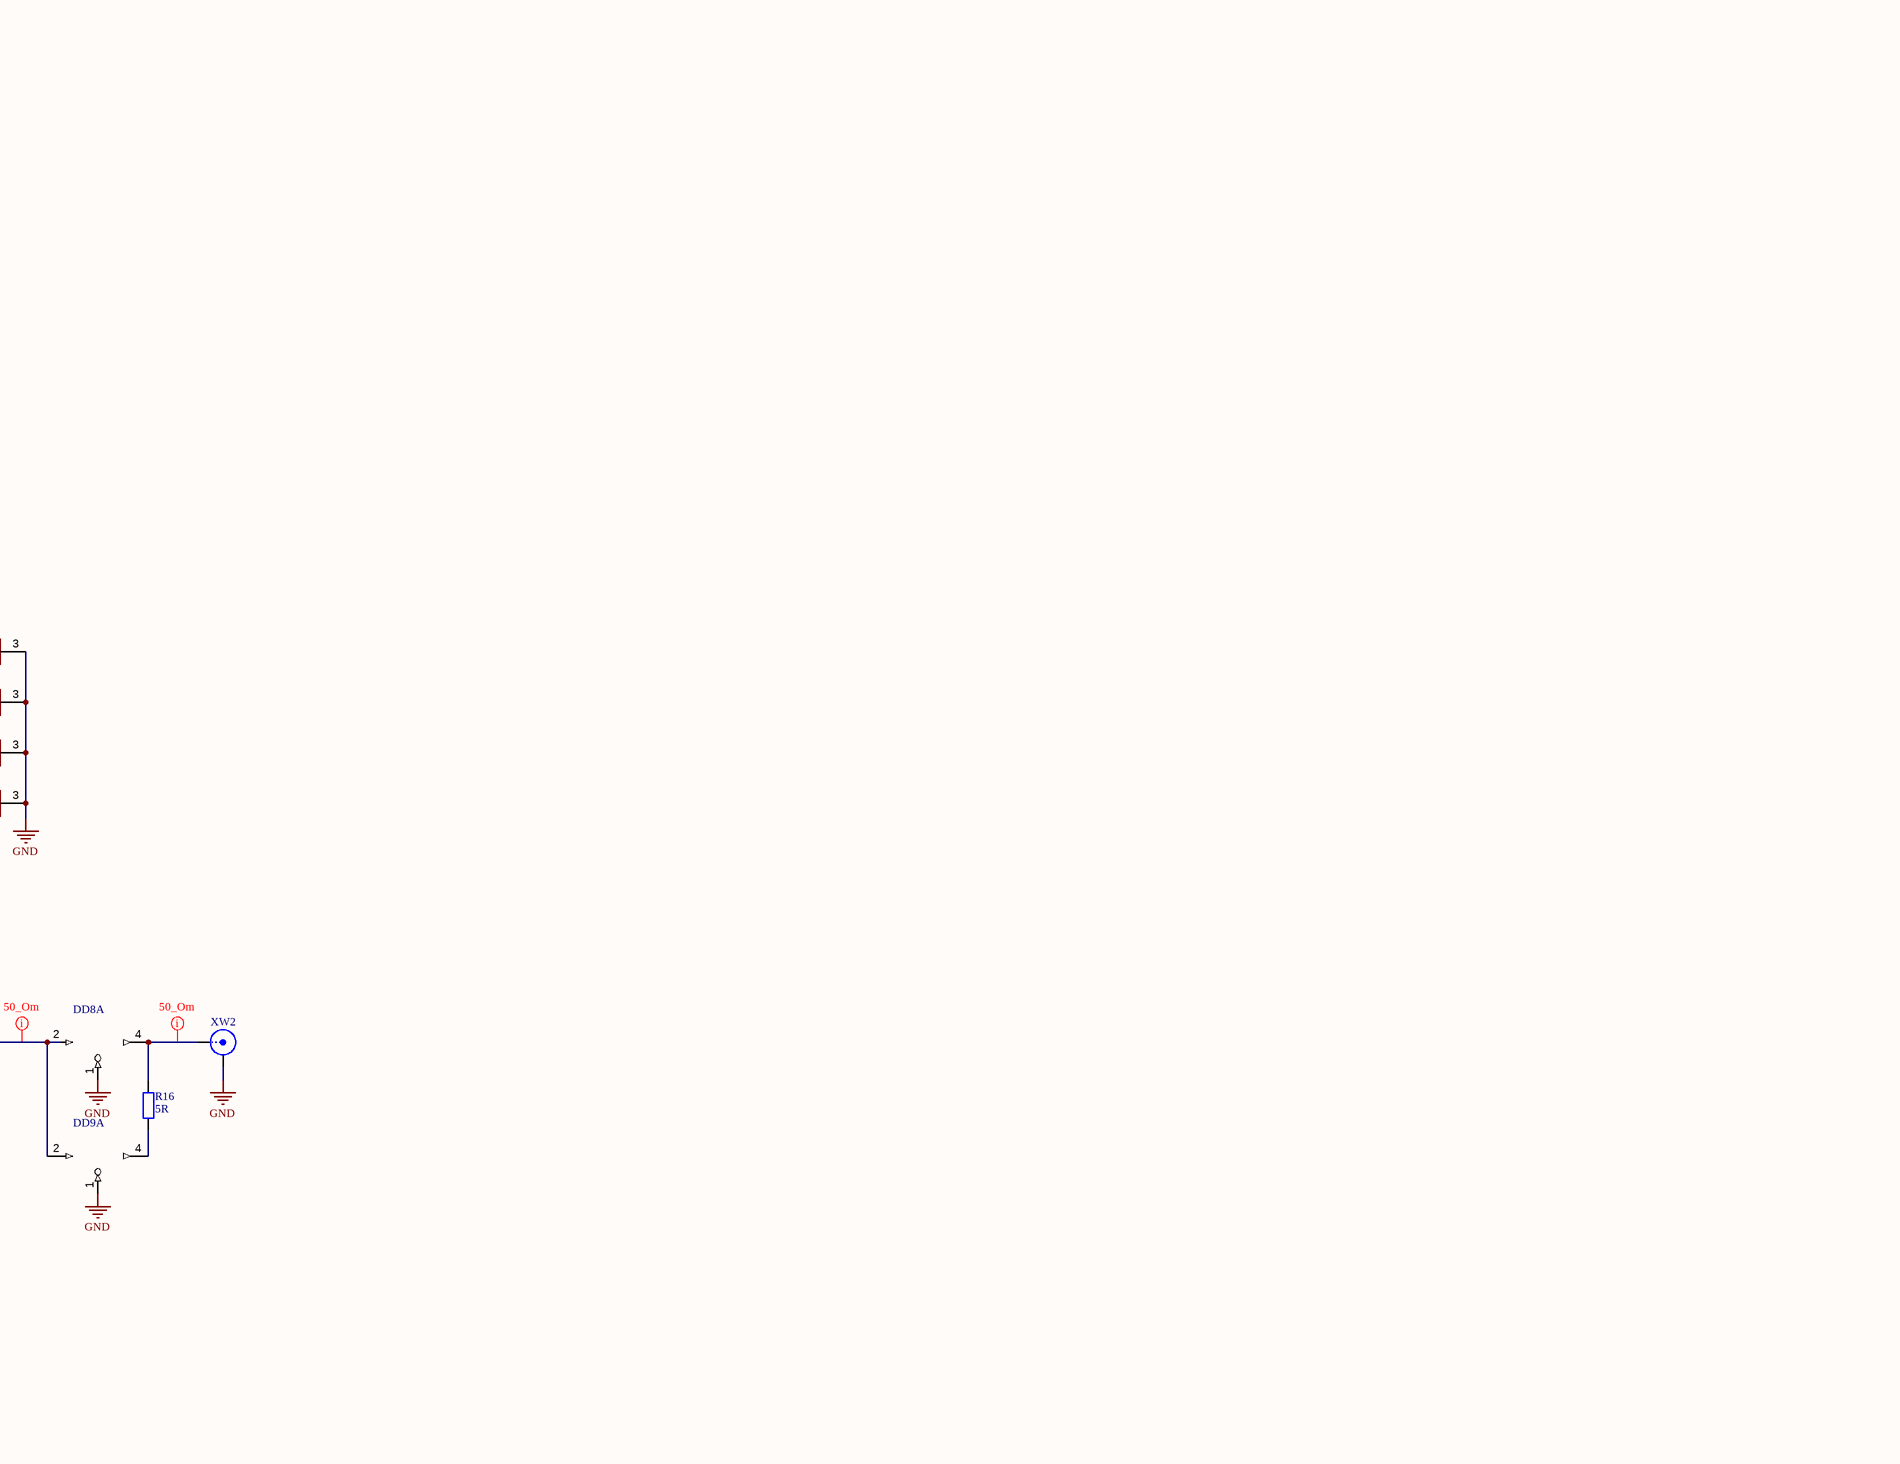
[diagram p11: Synthesizer.SchDoc, bottom column 4 of 4]

(export (version "E")
  (design (tool "Eeschema 10.0.6"))
  (components
    (comp (ref "C1")
      (value "100pF")
      (footprint "SMD 0402 (1005) max")
      (description "Capacitor")
      (fields (field (name "TOLERANCE") "±10%") (field (name "Comment") "Capacitors"))
      (libsource (lib "Capacitors") (part "Capacitors"))
    )
    (comp (ref "C2")
      (value "0.1uF")
      (footprint "SMD 0603 (1608) min")
      (description "Capacitor")
      (fields (field (name "TOLERANCE") "±10%") (field (name "Comment") "Capacitors"))
      (libsource (lib "Capacitors") (part "Capacitors"))
    )
    (comp (ref "C3")
      (value "10pF")
      (footprint "SMD 0603 (1608) min")
      (description "Capacitor")
      (fields (field (name "TOLERANCE") "±10%") (field (name "Comment") "Capacitors"))
      (libsource (lib "Capacitors") (part "Capacitors"))
    )
    (comp (ref "C4")
      (value "0.1uF")
      (footprint "SMD 0603 (1608) min")
      (description "Capacitor")
      (fields (field (name "TOLERANCE") "±10%") (field (name "Comment") "Capacitors"))
      (libsource (lib "Capacitors") (part "Capacitors"))
    )
    (comp (ref "C5")
      (value "10pF")
      (footprint "SMD 0603 (1608) min")
      (description "Capacitor")
      (fields (field (name "TOLERANCE") "±10%") (field (name "Comment") "Capacitors"))
      (libsource (lib "Capacitors") (part "Capacitors"))
    )
    (comp (ref "C6")
      (value "0.1uF")
      (footprint "SMD 0603 (1608) min")
      (description "Capacitor")
      (fields (field (name "TOLERANCE") "±10%") (field (name "Comment") "Capacitors"))
      (libsource (lib "Capacitors") (part "Capacitors"))
    )
    (comp (ref "C7")
      (value "10pF")
      (footprint "SMD 0603 (1608) min")
      (description "Capacitor")
      (fields (field (name "TOLERANCE") "±10%") (field (name "Comment") "Capacitors"))
      (libsource (lib "Capacitors") (part "Capacitors"))
    )
    (comp (ref "C8")
      (value "0.1uF")
      (footprint "SMD 0603 (1608) min")
      (description "Capacitor")
      (fields (field (name "TOLERANCE") "±10%") (field (name "Comment") "Capacitors"))
      (libsource (lib "Capacitors") (part "Capacitors"))
    )
    (comp (ref "C9")
      (value "10pF")
      (footprint "SMD 0603 (1608) min")
      (description "Capacitor")
      (fields (field (name "TOLERANCE") "±10%") (field (name "Comment") "Capacitors"))
      (libsource (lib "Capacitors") (part "Capacitors"))
    )
    (comp (ref "C10")
      (value "0.1uF")
      (footprint "SMD 0603 (1608) min")
      (description "Capacitor")
      (fields (field (name "TOLERANCE") "±10%") (field (name "Comment") "Capacitors"))
      (libsource (lib "Capacitors") (part "Capacitors"))
    )
    (comp (ref "C11")
      (value "10pF")
      (footprint "SMD 0603 (1608) min")
      (description "Capacitor")
      (fields (field (name "TOLERANCE") "±10%") (field (name "Comment") "Capacitors"))
      (libsource (lib "Capacitors") (part "Capacitors"))
    )
    (comp (ref "C12")
      (value "0.1uF")
      (footprint "SMD 0603 (1608) min")
      (description "Capacitor")
      (fields (field (name "TOLERANCE") "±10%") (field (name "Comment") "Capacitors"))
      (libsource (lib "Capacitors") (part "Capacitors"))
    )
    (comp (ref "C13")
      (value "10pF")
      (footprint "SMD 0603 (1608) min")
      (description "Capacitor")
      (fields (field (name "TOLERANCE") "±10%") (field (name "Comment") "Capacitors"))
      (libsource (lib "Capacitors") (part "Capacitors"))
    )
    (comp (ref "C14")
      (value "0.1uF")
      (footprint "SMD 0603 (1608) min")
      (description "Capacitor")
      (fields (field (name "TOLERANCE") "±10%") (field (name "Comment") "Capacitors"))
      (libsource (lib "Capacitors") (part "Capacitors"))
    )
    (comp (ref "C15")
      (value "10pF")
      (footprint "SMD 0603 (1608) min")
      (description "Capacitor")
      (fields (field (name "TOLERANCE") "±10%") (field (name "Comment") "Capacitors"))
      (libsource (lib "Capacitors") (part "Capacitors"))
    )
    (comp (ref "C16")
      (value "0.1uF")
      (footprint "SMD 0603 (1608) min")
      (description "Capacitor")
      (fields (field (name "TOLERANCE") "±10%") (field (name "Comment") "Capacitors"))
      (libsource (lib "Capacitors") (part "Capacitors"))
    )
    (comp (ref "C17")
      (value "10pF")
      (footprint "SMD 0603 (1608) min")
      (description "Capacitor")
      (fields (field (name "TOLERANCE") "±10%") (field (name "Comment") "Capacitors"))
      (libsource (lib "Capacitors") (part "Capacitors"))
    )
    (comp (ref "C18")
      (value "39nF")
      (footprint "SMD 0603 (1608) min")
      (description "Capacitor")
      (fields (field (name "TOLERANCE") "±10%") (field (name "Comment") "Capacitors"))
      (libsource (lib "Capacitors") (part "Capacitors"))
    )
    (comp (ref "C19")
      (value "1200pF")
      (footprint "SMD 0603 (1608) min")
      (description "Capacitor")
      (fields (field (name "TOLERANCE") "±10%") (field (name "Comment") "Capacitors"))
      (libsource (lib "Capacitors") (part "Capacitors"))
    )
    (comp (ref "C20")
      (value "0.1uF")
      (footprint "SMD 0603 (1608) min")
      (description "Capacitor")
      (fields (field (name "TOLERANCE") "±10%") (field (name "Comment") "Capacitors"))
      (libsource (lib "Capacitors") (part "Capacitors"))
    )
    (comp (ref "C21")
      (value "10nF")
      (footprint "SMD 0603 (1608) min")
      (description "Capacitor")
      (fields (field (name "TOLERANCE") "±10%") (field (name "Comment") "Capacitors"))
      (libsource (lib "Capacitors") (part "Capacitors"))
    )
    (comp (ref "C22")
      (value "0.1uF")
      (footprint "SMD 0603 (1608) min")
      (description "Capacitor")
      (fields (field (name "TOLERANCE") "±10%") (field (name "Comment") "Capacitors"))
      (libsource (lib "Capacitors") (part "Capacitors"))
    )
    (comp (ref "C23")
      (value "100nF")
      (footprint "0805 (2012)")
      (description "Ceramic Capacitor  0.1uF 100V")
      (fields
        (field (name "MANUFACTURER") "Vishay Vitramon")
        (field (name "TOLERANCE") "10%")
        (field (name "РАЗРАБОТЧИК") "Богатов Алексей")
      )
      (libsource (lib "Конденсаторы") (part "VJ0805Y104KXBTW1BC"))
    )
    (comp (ref "C24")
      (value "10uF")
      (footprint "0805 (2012)")
      (description "Ceramic Capacitors 10uF 10volts")
      (fields
        (field (name "MANUFACTURER") "Vishay Vitramon")
        (field (name "MANUFACTURER PART NUMBER") "VJ0805V106ZXQTW1BC")
        (field (name "РАЗРАБОТЧИК") "Богатов Алексей")
      )
      (libsource (lib "Конденсаторы") (part "VJ0805V106ZXQTW1BC"))
    )
    (comp (ref "C25")
      (value "100pF")
      (footprint "1414 (Min1)")
      (description "Multilayer Ceramic Capacitors MLCC")
      (fields
        (field (name "TOLERANCE") "±5%")
        (field (name "MANUFACTURER") "American Technical Ceramics")
        (field (name "РАЗРАБОТЧИК") "Леткин Д.С.")
      )
      (libsource (lib "Конденсаторы") (part "100A101JT150XT"))
    )
    (comp (ref "C26")
      (value "100pF")
      (footprint "1414 (Min1)")
      (description "Multilayer Ceramic Capacitors MLCC")
      (fields
        (field (name "TOLERANCE") "±5%")
        (field (name "MANUFACTURER") "American Technical Ceramics")
        (field (name "РАЗРАБОТЧИК") "Леткин Д.С.")
      )
      (libsource (lib "Конденсаторы") (part "100A101JT150XT"))
    )
    (comp (ref "C27")
      (value "20nF")
      (footprint "1414 (Min1)")
      (description "Multilayer Ceramic Capacitors MLCC")
      (fields
        (field (name "TOLERANCE") "±5%")
        (field (name "MANUFACTURER") "American Technical Ceramics")
        (field (name "РАЗРАБОТЧИК") "Леткин Д.С.")
      )
      (libsource (lib "Конденсаторы") (part "100A101JT150XT"))
    )
    (comp (ref "C28")
      (value "100pF")
      (footprint "0603 (1608)")
      (description "Ceramic Capacitors 0.1uF 50volts")
      (fields
        (field (name "MANUFACTURER") "Vishay Semiconductors")
        (field (name "MANUFACTURER PART NUMBER") "VJ0603Y104KXAAC")
        (field (name "РАЗРАБОТЧИК") "Богатов Алексей")
      )
      (libsource (lib "Vishay") (part "VJ0603Y104KXAAC"))
    )
    (comp (ref "C29")
      (value "0.1uF")
      (footprint "SMD 0603 (1608) min")
      (description "Capacitor")
      (fields (field (name "TOLERANCE") "±10%") (field (name "Comment") "Capacitors"))
      (libsource (lib "Capacitors") (part "Capacitors"))
    )
    (comp (ref "C30")
      (value "10nF")
      (footprint "SMD 0603 (1608) min")
      (description "Capacitor")
      (fields (field (name "TOLERANCE") "±10%") (field (name "Comment") "Capacitors"))
      (libsource (lib "Capacitors") (part "Capacitors"))
    )
    (comp (ref "C31")
      (value "10nF")
      (footprint "SMD 0603 (1608) min")
      (description "Capacitor")
      (fields (field (name "TOLERANCE") "±10%") (field (name "Comment") "Capacitors"))
      (libsource (lib "Capacitors") (part "Capacitors"))
    )
    (comp (ref "C32")
      (value "0.1uF")
      (footprint "SMD 0603 (1608) min")
      (description "Capacitor")
      (fields (field (name "TOLERANCE") "±10%") (field (name "Comment") "Capacitors"))
      (libsource (lib "Capacitors") (part "Capacitors"))
    )
    (comp (ref "C33")
      (value "100pF")
      (footprint "SMD 0402 (1005) max")
      (description "Capacitor")
      (fields (field (name "TOLERANCE") "±10%") (field (name "Comment") "Capacitors"))
      (libsource (lib "Capacitors") (part "Capacitors"))
    )
    (comp (ref "C34")
      (value "100pF")
      (footprint "SMD 0402 (1005) max")
      (description "Capacitor")
      (fields (field (name "TOLERANCE") "±10%") (field (name "Comment") "Capacitors"))
      (libsource (lib "Capacitors") (part "Capacitors"))
    )
    (comp (ref "C35")
      (value "1uF")
      (footprint "SMD 0603 (1608) min")
      (description "Capacitor")
      (fields (field (name "TOLERANCE") "±10%") (field (name "Comment") "Capacitors"))
      (libsource (lib "altium-import") (part "root_2_Capacitors_"))
    )
    (comp (ref "C36")
      (value "0.01uF")
      (footprint "SMD 0603 (1608) min")
      (description "Capacitor")
      (fields (field (name "TOLERANCE") "±10%") (field (name "Comment") "Capacitors"))
      (libsource (lib "altium-import") (part "root_0_Capacitors_"))
    )
    (comp (ref "C37")
      (value "0.1uF")
      (footprint "SMD 0603 (1608) min")
      (description "Capacitor")
      (fields (field (name "TOLERANCE") "±10%") (field (name "Comment") "Capacitors"))
      (libsource (lib "altium-import") (part "root_1_Capacitors_"))
    )
    (comp (ref "C38")
      (value "10pF")
      (footprint "SMD 0603 (1608) min")
      (description "Capacitor")
      (fields (field (name "TOLERANCE") "±10%") (field (name "Comment") "Capacitors"))
      (libsource (lib "altium-import") (part "root_1_Capacitors_"))
    )
    (comp (ref "C39")
      (value "0.1uF")
      (footprint "SMD 0603 (1608) min")
      (description "Capacitor")
      (fields (field (name "TOLERANCE") "±10%") (field (name "Comment") "Capacitors"))
      (libsource (lib "altium-import") (part "root_1_Capacitors_"))
    )
    (comp (ref "C40")
      (value "10pF")
      (footprint "SMD 0603 (1608) min")
      (description "Capacitor")
      (fields (field (name "TOLERANCE") "±10%") (field (name "Comment") "Capacitors"))
      (libsource (lib "altium-import") (part "root_1_Capacitors_"))
    )
    (comp (ref "C41")
      (value "0.1uF")
      (footprint "SMD 0603 (1608) min")
      (description "Capacitor")
      (fields (field (name "TOLERANCE") "±10%") (field (name "Comment") "Capacitors"))
      (libsource (lib "altium-import") (part "root_1_Capacitors_"))
    )
    (comp (ref "C42")
      (value "100nF")
      (footprint "0805 (2012)")
      (description "Ceramic Capacitor  0.1uF 100V")
      (fields
        (field (name "MANUFACTURER") "Vishay Vitramon")
        (field (name "TOLERANCE") "10%")
        (field (name "РАЗРАБОТЧИК") "Богатов Алексей")
      )
      (libsource (lib "Конденсаторы") (part "VJ0805Y104KXBTW1BC"))
    )
    (comp (ref "C43")
      (value "10uF 25V")
      (footprint "Electrolytic D=8mm H=11.5mm")
      (description "Capacitor Polarized")
      (fields (field (name "TOLERANCE") "±10%"))
      (libsource (lib "Конденсаторы") (part "Capacitor Polarized"))
    )
    (comp (ref "C44")
      (value "0.1uF")
      (footprint "SMD 0603 (1608) min")
      (description "Capacitor")
      (fields (field (name "TOLERANCE") "±10%") (field (name "Comment") "Capacitors"))
      (libsource (lib "altium-import") (part "root_3_Capacitors_"))
    )
    (comp (ref "C45")
      (value "0.1uF")
      (footprint "SMD 0603 (1608) min")
      (description "Capacitor")
      (fields (field (name "TOLERANCE") "±10%") (field (name "Comment") "Capacitors"))
      (libsource (lib "altium-import") (part "root_2_Capacitors_"))
    )
    (comp (ref "C46")
      (value "0.1uF")
      (footprint "SMD 0603 (1608) min")
      (description "Capacitor")
      (fields (field (name "TOLERANCE") "±10%") (field (name "Comment") "Capacitors"))
      (libsource (lib "altium-import") (part "root_2_Capacitors_"))
    )
    (comp (ref "C47")
      (value "0.1uF")
      (footprint "SMD 0603 (1608) min")
      (description "Capacitor")
      (fields (field (name "TOLERANCE") "±10%") (field (name "Comment") "Capacitors"))
      (libsource (lib "altium-import") (part "root_2_Capacitors_"))
    )
    (comp (ref "C48")
      (value "0.1uF")
      (footprint "SMD 0603 (1608) min")
      (description "Capacitor")
      (fields (field (name "TOLERANCE") "±10%") (field (name "Comment") "Capacitors"))
      (libsource (lib "altium-import") (part "root_2_Capacitors_"))
    )
    (comp (ref "DA1")
      (value "LF50ABDT-TR")
      (footprint "DPAK228P970X238-3N")
      (description "IC REG LDO 5V 0.5A DPAK")
      (fields (field (name "MANUFACTURER") "STMicroelectronics") (field (name "РАЗРАБОТЧИК") "Леткин Д."))
      (libsource (lib "altium-import") (part "root_0_LF50ABDT-TR_"))
    )
    (comp (ref "DD1")
      (value "ADF4351BCPZ")
      (footprint "LFCSP-32  Long Pin - with VIA")
      (description "Phase Locked Loops - PLL WB Synthesizer w/ Intg VCO")
      (fields (field (name "MANUFACTURER") "Analog Devices") (field (name "РАЗРАБОТЧИК") "Леткин Д.С."))
      (libsource (lib "Микросхемы") (part "ADF4351BCPZ"))
    )
    (comp (ref "DD2")
      (value "BD1631J50100AHF")
      (footprint "0805_a")
      (fields (field (name "MANUFACTURER") "Anaren") (field (name "РАЗРАБОТЧИК") "Леткин Д.С."))
      (libsource (lib "Микросхемы") (part "BD1631J50100AHF"))
    )
    (comp (ref "DD3")
      (value "AG303-86G")
      (footprint "SOT-86 (Min)")
      (fields (field (name "MANUFACTURER") "TriQuint") (field (name "РАЗРАБОЧИК") "Леткин Д.С."))
      (libsource (lib "Микросхемы") (part "AG303-86G"))
    )
    (comp (ref "DD4")
      (value "HMC988LP3E")
      (footprint "QFN16M.5 Long Pin")
      (fields (field (name "MANUFACTURER") "Analog Devices") (field (name "РАЗРАБОТЧИК") "Жабин И."))
      (libsource (lib "Микросхемы") (part "HMC988LP3E"))
    )
    (comp (ref "DD5")
      (value "SN74AHCT1G125DBVR")
      (footprint "SOT-23-5")
      (description "SINGLE BUS BUFFER GATE WITH 3-STATE OUTPUT")
      (fields
        (field (name "MANUFACTURER") "Texas Instruments")
        (field (name "BASE PART NUMBER") "74AHCT1G125")
      )
      (libsource (lib "Texas_Instruments") (part "SN74AHCT1G125DBVR"))
    )
    (comp (ref "DD6")
      (value "SN74AHCT1G125DBVR")
      (footprint "SOT-23-5")
      (description "SINGLE BUS BUFFER GATE WITH 3-STATE OUTPUT")
      (fields
        (field (name "MANUFACTURER") "Texas Instruments")
        (field (name "BASE PART NUMBER") "74AHCT1G125")
      )
      (libsource (lib "Texas_Instruments") (part "SN74AHCT1G125DBVR"))
    )
    (comp (ref "DD7")
      (value "74AUP1G74")
      (footprint "SOT765-1")
      (description "Low-power D-type flip-flop with set and reset; positive-edge\r\ntrigger")
      (fields (field (name "MANUFACTURER") "NXP Semiconductors") (field (name "РАЗРАБОТЧИК") "Жабин И."))
      (libsource (lib "altium-import") (part "root_0_74AUP1G74_"))
    )
    (comp (ref "DD8")
      (value "SN74AHCT1G125DBVR")
      (footprint "SOT-23-5")
      (description "SINGLE BUS BUFFER GATE WITH 3-STATE OUTPUT")
      (fields
        (field (name "MANUFACTURER") "Texas Instruments")
        (field (name "BASE PART NUMBER") "74AHCT1G125")
      )
      (libsource (lib "Texas_Instruments") (part "SN74AHCT1G125DBVR"))
    )
    (comp (ref "DD9")
      (value "SN74AHCT1G125DBVR")
      (footprint "SOT-23-5")
      (description "SINGLE BUS BUFFER GATE WITH 3-STATE OUTPUT")
      (fields
        (field (name "MANUFACTURER") "Texas Instruments")
        (field (name "BASE PART NUMBER") "74AHCT1G125")
      )
      (libsource (lib "Texas_Instruments") (part "SN74AHCT1G125DBVR"))
    )
    (comp (ref "L1")
      (value "0603HP-18NXJE")
      (footprint "0603HP")
      (description "Ceramic Chip Inductors")
      (fields (field (name "MANUFACTURER") "Coilcraft") (field (name "РАЗРАБОТЧИК") "Леткин Д.С."))
      (libsource (lib "Катушки_индуктивности") (part "0603HP-18NXJE"))
    )
    (comp (ref "L2")
      (value "0603HP-18NXJE")
      (footprint "0603HP")
      (description "Ceramic Chip Inductors")
      (fields
        (field (name "MANUFACTURER") "Coilcraft")
        (field (name "MANUFACTURER PART NUMBER") "0603HP-18NXJE")
        (field (name "РАЗРАБОТЧИК") "Леткин Д.С.")
      )
      (libsource (lib "Катушки_индуктивности") (part "0603HP-18NXJE"))
    )
    (comp (ref "L3")
      (value "0603HP-18NXJE")
      (footprint "0603HP")
      (description "Ceramic Chip Inductors")
      (fields (field (name "MANUFACTURER") "Coilcraft") (field (name "РАЗРАБОТЧИК") "Леткин Д.С."))
      (libsource (lib "Катушки_индуктивности") (part "0603HP-18NXJE"))
    )
    (comp (ref "L4")
      (value "0603HP-18NXJE")
      (footprint "0603HP")
      (description "Ceramic Chip Inductors")
      (fields (field (name "MANUFACTURER") "Coilcraft") (field (name "РАЗРАБОТЧИК") "Леткин Д.С."))
      (libsource (lib "") (part "0603HP-18NXJE_1"))
    )
    (comp (ref "LG1")
      (value "1296.1004")
      (footprint "1296.1004")
      (description "световод на плату под 4 светодиода")
      (fields (field (name "MANUFACTURER") "Mentor"))
      (libsource (lib "Прочее") (part "1296.1004"))
    )
    (comp (ref "R1")
      (value "1R")
      (footprint "Resistor SMD 0603 (1608) min")
      (description "Resistor")
      (libsource (lib "Devices") (part "Resistors"))
    )
    (comp (ref "R2")
      (value "4K7")
      (footprint "0603R-4K7")
      (description "GENERIC RESISTOR 0603")
      (fields
        (field (name "MANUFACTURER") "Stackpole Electronics Inc")
        (field (name "MANUFACTURER PART NUMBER") "RMCF 1/16 4.7K 1% R")
      )
      (libsource (lib "Resistors") (part "0603R-4K7"))
    )
    (comp (ref "R3")
      (value "680")
      (footprint "0603R-4K7")
      (description "GENERIC RESISTOR 0603")
      (fields
        (field (name "MANUFACTURER") "Stackpole Electronics Inc")
        (field (name "MANUFACTURER PART NUMBER") "RMCF 1/16 4.7K 1% R")
      )
      (libsource (lib "Resistors") (part "0603R-4K7"))
    )
    (comp (ref "R4")
      (value "120")
      (footprint "0603R-4K7")
      (description "GENERIC RESISTOR 0603")
      (fields
        (field (name "MANUFACTURER") "Stackpole Electronics Inc")
        (field (name "MANUFACTURER PART NUMBER") "RMCF 1/16 4.7K 1% R")
      )
      (libsource (lib "Resistors") (part "0603R-4K7"))
    )
    (comp (ref "R5")
      (value "360")
      (footprint "Resistor SMD 0603 (1608) min")
      (description "Resistor")
      (libsource (lib "Devices") (part "Resistors"))
    )
    (comp (ref "R6")
      (value "51R")
      (footprint "0603R-100")
      (description "GENERIC RESISTOR 0603")
      (fields
        (field (name "MANUFACTURER PART NUMBER") "RMCF 1/16 100 1% R")
        (field (name "MANUFACTURER") "Stackpole Electronics Inc")
      )
      (libsource (lib "Resistors") (part "0603R-100"))
    )
    (comp (ref "R7")
      (value "100R")
      (footprint "0603R-100")
      (description "GENERIC RESISTOR 0603")
      (fields
        (field (name "MANUFACTURER PART NUMBER") "RMCF 1/16 100 1% R")
        (field (name "MANUFACTURER") "Stackpole Electronics Inc")
      )
      (libsource (lib "Resistors") (part "0603R-100"))
    )
    (comp (ref "R8")
      (value "100R")
      (footprint "0603R-100")
      (description "GENERIC RESISTOR 0603")
      (fields
        (field (name "MANUFACTURER PART NUMBER") "RMCF 1/16 100 1% R")
        (field (name "MANUFACTURER") "Stackpole Electronics Inc")
      )
      (libsource (lib "Resistors") (part "0603R-100"))
    )
    (comp (ref "R9")
      (value "100R")
      (footprint "0603R-100")
      (description "GENERIC RESISTOR 0603")
      (fields
        (field (name "MANUFACTURER PART NUMBER") "RMCF 1/16 100 1% R")
        (field (name "MANUFACTURER") "Stackpole Electronics Inc")
      )
      (libsource (lib "Resistors") (part "0603R-100"))
    )
    (comp (ref "R10")
      (value "10k")
      (footprint "0603R-0R")
      (description "GENERIC JUMPER 0603")
      (fields
        (field (name "MANUFACTURER") "Stackpole Electronics Inc")
        (field (name "MANUFACTURER PART NUMBER") "RMC 1/16 0 G")
      )
      (libsource (lib "Resistors") (part "0603R-0R"))
    )
    (comp (ref "R11")
      (value "10k")
      (footprint "0603R-0R")
      (description "GENERIC JUMPER 0603")
      (fields
        (field (name "MANUFACTURER") "Stackpole Electronics Inc")
        (field (name "MANUFACTURER PART NUMBER") "RMC 1/16 0 G")
      )
      (libsource (lib "Resistors") (part "0603R-0R"))
    )
    (comp (ref "R12")
      (value "10k")
      (footprint "0603R-0R")
      (description "GENERIC JUMPER 0603")
      (fields
        (field (name "MANUFACTURER") "Stackpole Electronics Inc")
        (field (name "MANUFACTURER PART NUMBER") "RMC 1/16 0 G")
      )
      (libsource (lib "Resistors") (part "0603R-0R"))
    )
    (comp (ref "R13")
      (value "X")
      (footprint "0603R-0R")
      (description "GENERIC JUMPER 0603")
      (fields
        (field (name "MANUFACTURER") "Stackpole Electronics Inc")
        (field (name "MANUFACTURER PART NUMBER") "RMC 1/16 0 G")
      )
      (libsource (lib "Resistors") (part "0603R-0R"))
    )
    (comp (ref "R14")
      (value "0")
      (footprint "0603R-0R")
      (description "GENERIC JUMPER 0603")
      (fields
        (field (name "MANUFACTURER") "Stackpole Electronics Inc")
        (field (name "MANUFACTURER PART NUMBER") "RMC 1/16 0 G")
      )
      (libsource (lib "Resistors") (part "0603R-0R"))
    )
    (comp (ref "R15")
      (value "X")
      (footprint "0603R-0R")
      (description "GENERIC JUMPER 0603")
      (fields
        (field (name "MANUFACTURER") "Stackpole Electronics Inc")
        (field (name "MANUFACTURER PART NUMBER") "RMC 1/16 0 G")
      )
      (libsource (lib "Resistors") (part "0603R-0R"))
    )
    (comp (ref "R16")
      (value "5R")
      (footprint "0603R-0R")
      (description "GENERIC JUMPER 0603")
      (fields
        (field (name "MANUFACTURER") "Stackpole Electronics Inc")
        (field (name "MANUFACTURER PART NUMBER") "RMC 1/16 0 G")
      )
      (libsource (lib "Resistors") (part "0603R-0R"))
    )
    (comp (ref "R17")
      (value "10k")
      (footprint "0603R-0R")
      (description "GENERIC JUMPER 0603")
      (fields
        (field (name "MANUFACTURER") "Stackpole Electronics Inc")
        (field (name "MANUFACTURER PART NUMBER") "RMC 1/16 0 G")
      )
      (libsource (lib "Resistors") (part "0603R-0R"))
    )
    (comp (ref "R18")
      (value "0")
      (footprint "0603R-0R")
      (description "GENERIC JUMPER 0603")
      (fields
        (field (name "MANUFACTURER") "Stackpole Electronics Inc")
        (field (name "MANUFACTURER PART NUMBER") "RMC 1/16 0 G")
      )
      (libsource (lib "Resistors") (part "0603R-0R"))
    )
    (comp (ref "R19")
      (value "0")
      (footprint "0603R-0R")
      (description "GENERIC JUMPER 0603")
      (fields
        (field (name "MANUFACTURER") "Stackpole Electronics Inc")
        (field (name "MANUFACTURER PART NUMBER") "RMC 1/16 0 G")
      )
      (libsource (lib "Resistors") (part "0603R-0R"))
    )
    (comp (ref "R20")
      (value "0")
      (footprint "0603R-0R")
      (description "GENERIC JUMPER 0603")
      (fields
        (field (name "MANUFACTURER") "Stackpole Electronics Inc")
        (field (name "MANUFACTURER PART NUMBER") "RMC 1/16 0 G")
      )
      (libsource (lib "Resistors") (part "0603R-0R"))
    )
    (comp (ref "U1")
      (value "LD1117S33TR")
      (footprint "SOT-223")
      (fields
        (field (name "MANUFACTURER") "STMicroelectronics")
        (field (name "MANUFACTURER PART NUMBER") "LD1117S50TR")
        (field (name "BASE PART NUMBER") "LD1117")
      )
      (libsource (lib "ST_Microelectronics") (part "LD1117S50TR"))
    )
    (comp (ref "U2")
      (value "SN65ELT21D")
      (footprint "DGK8_L")
      (fields (field (name "MANUFACTURER") "Texas Instruments"))
      (libsource (lib "TI Interface LVDS M-LVDS ECL CML") (part "SN65ELT21D"))
    )
    (comp (ref "XP2")
      (value "09 23 148 6921")
      (footprint "09 23 148 6921")
      (description "DIN-Signal 2C048MS-1C1-2")
      (fields
        (field (name "MANUFACTURER") "HARTING")
        (field (name "MANUFACTURER PART NUMBER") "09231486921")
        (field (name "РАЗРАБОТЧИК") "Леткин Д.")
      )
      (libsource (lib "Harting") (part "09 23 148 6921"))
    )
    (comp (ref "XW1")
      (value "J01151A0201")
      (footprint "J01151A0201")
      (description "Telegartner Right Angle 50Ohm Thru Hole SMA Connector,  jack,  Solder Termination")
      (fields (field (name "MANUFACTURER") "Telegartner"))
      (libsource (lib "Telegartner") (part "J01151A0201"))
    )
    (comp (ref "XW2")
      (value "J01151A0201")
      (footprint "J01151A0201")
      (description "Telegartner Right Angle 50Ohm Thru Hole SMA Connector,  jack,  Solder Termination")
      (fields (field (name "MANUFACTURER") "Telegartner"))
      (libsource (lib "Telegartner") (part "J01151A0201"))
    )
    (comp (ref "ZQ1")
      (value "ГК1010-TK")
      (footprint "DIL-8")
      (description "Генераторы кварцевые программируемые")
      (fields (field (name "MANUFACTURER") "БМГ ПЛЮС") (field (name "РАЗРАБОТЧИК") "Леткин Д.С."))
      (libsource (lib "Фильтры") (part "ГК1010-TK"))
    )
  )
  (nets
    (net (code "1") (name "+3.3V") (class "Default")
      (node (ref "C10") (pin "1") (pinfunction "1_1") (pintype "passive"))
      (node (ref "C11") (pin "2") (pinfunction "2_2") (pintype "passive"))
      (node (ref "C12") (pin "1") (pinfunction "1_1") (pintype "passive"))
      (node (ref "C13") (pin "2") (pinfunction "2_2") (pintype "passive"))
      (node (ref "C14") (pin "1") (pinfunction "1_1") (pintype "passive"))
      (node (ref "C15") (pin "2") (pinfunction "2_2") (pintype "passive"))
      (node (ref "C16") (pin "1") (pinfunction "1_1") (pintype "passive"))
      (node (ref "C17") (pin "2") (pinfunction "2_2") (pintype "passive"))
      (node (ref "C20") (pin "1") (pinfunction "1_1") (pintype "passive"))
      (node (ref "C21") (pin "2") (pinfunction "2_2") (pintype "passive"))
      (node (ref "C22") (pin "2") (pinfunction "2_2") (pintype "passive"))
      (node (ref "C24") (pin "2") (pinfunction "2_2") (pintype "passive"))
      (node (ref "C29") (pin "1") (pinfunction "1_1") (pintype "passive"))
      (node (ref "C30") (pin "2") (pinfunction "2_2") (pintype "passive"))
      (node (ref "C31") (pin "2") (pinfunction "2_2") (pintype "passive"))
      (node (ref "C32") (pin "1") (pinfunction "1_1") (pintype "passive"))
      (node (ref "C44") (pin "1") (pinfunction "1_1") (pintype "passive"))
      (node (ref "C8") (pin "1") (pinfunction "1_1") (pintype "passive"))
      (node (ref "C9") (pin "2") (pinfunction "2_2") (pintype "passive"))
      (node (ref "DD1") (pin "10") (pinfunction "AVDD_10") (pintype "power_in"))
      (node (ref "DD1") (pin "16") (pinfunction "VVCO_16") (pintype "power_in"))
      (node (ref "DD1") (pin "17") (pinfunction "VVCO_17") (pintype "power_in"))
      (node (ref "DD1") (pin "26") (pinfunction "PDBRF_26") (pintype "passive"))
      (node (ref "DD1") (pin "28") (pinfunction "DVDD_28") (pintype "power_in"))
      (node (ref "DD1") (pin "32") (pinfunction "SDVDD_32") (pintype "power_in"))
      (node (ref "DD1") (pin "4") (pinfunction "CE_4") (pintype "passive"))
      (node (ref "DD1") (pin "6") (pinfunction "VP_6") (pintype "power_in"))
      (node (ref "DD7") (pin "6") (pinfunction "~{RD}_6") (pintype "passive"))
      (node (ref "DD7") (pin "7") (pinfunction "~{SD}_7") (pintype "passive"))
      (node (ref "DD7") (pin "8") (pinfunction "VCC_8") (pintype "power_in"))
      (node (ref "L1") (pin "2") (pinfunction "2_2") (pintype "passive"))
      (node (ref "L3") (pin "2") (pinfunction "2_2") (pintype "passive"))
      (node (ref "L4") (pin "2") (pinfunction "2_2") (pintype "passive"))
      (node (ref "R13") (pin "2") (pinfunction "2_2") (pintype "passive"))
      (node (ref "U1") (pin "2") (pinfunction "OUT_2") (pintype "power_in"))
      (node (ref "ZQ1") (pin "2") (pinfunction "Управление_2") (pintype "passive"))
      (node (ref "ZQ1") (pin "6") (pinfunction "Питание_6") (pintype "passive"))
    )
    (net (code "2") (name "+5V") (class "Default")
      (node (ref "C37") (pin "2") (pinfunction "2_2") (pintype "passive"))
      (node (ref "C38") (pin "2") (pinfunction "2_2") (pintype "passive"))
      (node (ref "C41") (pin "2") (pinfunction "2_2") (pintype "passive"))
      (node (ref "C43") (pin "1") (pinfunction "1_1") (pintype "passive"))
      (node (ref "DA1") (pin "3") (pinfunction "OUT_3") (pintype "power_in"))
      (node (ref "DD4") (pin "16") (pinfunction "VDD5_16") (pintype "passive"))
      (node (ref "U2") (pin "8") (pinfunction "VCC_8") (pintype "power_in"))
    )
    (net (code "3") (name "+6V") (class "Default")
      (node (ref "C23") (pin "2") (pinfunction "2_2") (pintype "passive"))
      (node (ref "C42") (pin "2") (pinfunction "2_2") (pintype "passive"))
      (node (ref "C45") (pin "1") (pinfunction "1_1") (pintype "passive"))
      (node (ref "C46") (pin "1") (pinfunction "1_1") (pintype "passive"))
      (node (ref "C47") (pin "1") (pinfunction "1_1") (pintype "passive"))
      (node (ref "C48") (pin "1") (pinfunction "1_1") (pintype "passive"))
      (node (ref "DA1") (pin "1") (pinfunction "IN_1") (pintype "power_in"))
      (node (ref "DD5") (pin "5") (pinfunction "VCC_5") (pintype "power_in"))
      (node (ref "DD6") (pin "5") (pinfunction "VCC_5") (pintype "power_in"))
      (node (ref "DD8") (pin "5") (pinfunction "VCC_5") (pintype "power_in"))
      (node (ref "DD9") (pin "5") (pinfunction "VCC_5") (pintype "power_in"))
      (node (ref "R17") (pin "2") (pinfunction "2_2") (pintype "passive"))
      (node (ref "R6") (pin "2") (pinfunction "2_2") (pintype "passive"))
      (node (ref "U1") (pin "3") (pinfunction "IN_3") (pintype "power_in"))
      (node (ref "XP2") (pin "a1") (pinfunction "a1_a1") (pintype "passive"))
      (node (ref "XP2") (pin "b1") (pinfunction "b1_b1") (pintype "passive"))
      (node (ref "XP2") (pin "c1") (pinfunction "c1_c1") (pintype "passive"))
    )
    (net (code "4") (name "/CLK") (class "Default")
      (node (ref "DD1") (pin "1") (pinfunction "CLK_1") (pintype "input"))
      (node (ref "DD4") (pin "8") (pinfunction "SCK_8") (pintype "passive"))
      (node (ref "XP2") (pin "a15") (pinfunction "a15_a15") (pintype "passive"))
    )
    (net (code "5") (name "/CS") (class "Default")
      (node (ref "DD4") (pin "9") (pinfunction "SLE_9") (pintype "passive"))
      (node (ref "XP2") (pin "a11") (pinfunction "a11_a11") (pintype "passive"))
    )
    (net (code "6") (name "/DATA") (class "Default")
      (node (ref "DD1") (pin "2") (pinfunction "DATA_2") (pintype "input"))
      (node (ref "DD4") (pin "7") (pinfunction "SDI_7") (pintype "input"))
      (node (ref "XP2") (pin "a13") (pinfunction "a13_a13") (pintype "passive"))
    )
    (net (code "7") (name "/DIV_N") (class "Default")
      (node (ref "DD4") (pin "10") (pinfunction "~{DIVN}_10") (pintype "passive"))
      (node (ref "U2") (pin "3") (pinfunction "~{D}_3") (pintype "input"))
    )
    (net (code "8") (name "/DIV_P") (class "Default")
      (node (ref "DD4") (pin "11") (pinfunction "DIVP_11") (pintype "passive"))
      (node (ref "U2") (pin "2") (pinfunction "D_2") (pintype "input"))
    )
    (net (code "9") (name "/LD") (class "Default")
      (node (ref "DD1") (pin "25") (pinfunction "LD_25") (pintype "output"))
      (node (ref "XP2") (pin "b16") (pinfunction "b16_b16") (pintype "passive"))
    )
    (net (code "10") (name "/LE") (class "Default")
      (node (ref "DD1") (pin "3") (pinfunction "LE_3") (pintype "passive"))
      (node (ref "XP2") (pin "a12") (pinfunction "a12_a12") (pintype "passive"))
    )
    (net (code "11") (name "/LED_1") (class "Default")
      (node (ref "R20") (pin "2") (pinfunction "2_2") (pintype "passive"))
      (node (ref "XP2") (pin "c6") (pinfunction "c6_c6") (pintype "passive"))
    )
    (net (code "12") (name "/LED_2") (class "Default")
      (node (ref "R19") (pin "2") (pinfunction "2_2") (pintype "passive"))
      (node (ref "XP2") (pin "c8") (pinfunction "c8_c8") (pintype "passive"))
    )
    (net (code "13") (name "/LED_3") (class "Default")
      (node (ref "R18") (pin "2") (pinfunction "2_2") (pintype "passive"))
      (node (ref "XP2") (pin "c10") (pinfunction "c10_c10") (pintype "passive"))
    )
    (net (code "14") (name "/REF_IN") (class "Default")
      (node (ref "C1") (pin "1") (pinfunction "1_1") (pintype "passive"))
      (node (ref "ZQ1") (pin "4") (pinfunction "Выход_частоты_4") (pintype "passive"))
    )
    (net (code "15") (name "/RFOutA_N") (class "Default")
      (node (ref "DD1") (pin "13") (pinfunction "RFOUTA−_13") (pintype "output"))
      (node (ref "DD2") (pin "3") (pinfunction "Balanced_Port_3") (pintype "passive"))
    )
    (net (code "16") (name "/RFOutA_P") (class "Default")
      (node (ref "DD1") (pin "12") (pinfunction "RFOUTA+_12") (pintype "output"))
      (node (ref "DD2") (pin "4") (pinfunction "Balanced_Port_4") (pintype "passive"))
    )
    (net (code "17") (name "/RFOutB1_N") (class "Default")
      (node (ref "C34") (pin "2") (pinfunction "2_2") (pintype "passive"))
      (node (ref "DD4") (pin "2") (pinfunction "OSCP_2") (pintype "input"))
    )
    (net (code "18") (name "/RFOutB1_P") (class "Default")
      (node (ref "C33") (pin "2") (pinfunction "2_2") (pintype "passive"))
      (node (ref "DD4") (pin "3") (pinfunction "~{OSCN}_3") (pintype "input"))
    )
    (net (code "19") (name "/RFOutB_N") (class "Default")
      (node (ref "C34") (pin "1") (pinfunction "1_1") (pintype "passive"))
      (node (ref "DD1") (pin "15") (pinfunction "RFOUTB−_15") (pintype "output"))
      (node (ref "L4") (pin "1") (pinfunction "1_1") (pintype "passive"))
    )
    (net (code "20") (name "/RFOutB_P") (class "Default")
      (node (ref "C33") (pin "1") (pinfunction "1_1") (pintype "passive"))
      (node (ref "DD1") (pin "14") (pinfunction "RFOUTB+_14") (pintype "output"))
      (node (ref "L3") (pin "1") (pinfunction "1_1") (pintype "passive"))
    )
    (net (code "21") (name "/SPI_MISO") (class "Default")
      (node (ref "DD1") (pin "30") (pinfunction "MUXOUT_30") (pintype "output"))
      (node (ref "DD4") (pin "6") (pinfunction "GPO_6") (pintype "output"))
      (node (ref "XP2") (pin "a14") (pinfunction "a14_a14") (pintype "passive"))
    )
    (net (code "22") (name "/SW") (class "Default")
      (node (ref "R1") (pin "1") (pinfunction "1_1") (pintype "passive"))
      (node (ref "R4") (pin "2") (pinfunction "2_2") (pintype "passive"))
      (node (ref "R5") (pin "1") (pinfunction "1_1") (pintype "passive"))
    )
    (net (code "23") (name "/SYNC") (class "Default")
      (node (ref "R14") (pin "2") (pinfunction "2_2") (pintype "passive"))
      (node (ref "XP2") (pin "a10") (pinfunction "a10_a10") (pintype "passive"))
    )
    (net (code "24") (name "GND") (class "Default")
      (node (ref "C10") (pin "2") (pinfunction "2_2") (pintype "passive"))
      (node (ref "C11") (pin "1") (pinfunction "1_1") (pintype "passive"))
      (node (ref "C12") (pin "2") (pinfunction "2_2") (pintype "passive"))
      (node (ref "C13") (pin "1") (pinfunction "1_1") (pintype "passive"))
      (node (ref "C14") (pin "2") (pinfunction "2_2") (pintype "passive"))
      (node (ref "C15") (pin "1") (pinfunction "1_1") (pintype "passive"))
      (node (ref "C16") (pin "2") (pinfunction "2_2") (pintype "passive"))
      (node (ref "C17") (pin "1") (pinfunction "1_1") (pintype "passive"))
      (node (ref "C19") (pin "1") (pinfunction "1_1") (pintype "passive"))
      (node (ref "C2") (pin "2") (pinfunction "2_2") (pintype "passive"))
      (node (ref "C20") (pin "2") (pinfunction "2_2") (pintype "passive"))
      (node (ref "C21") (pin "1") (pinfunction "1_1") (pintype "passive"))
      (node (ref "C22") (pin "1") (pinfunction "1_1") (pintype "passive"))
      (node (ref "C23") (pin "1") (pinfunction "1_1") (pintype "passive"))
      (node (ref "C24") (pin "1") (pinfunction "1_1") (pintype "passive"))
      (node (ref "C27") (pin "2") (pinfunction "2_2") (pintype "passive"))
      (node (ref "C28") (pin "2") (pinfunction "2_2") (pintype "passive"))
      (node (ref "C29") (pin "2") (pinfunction "2_2") (pintype "passive"))
      (node (ref "C3") (pin "2") (pinfunction "2_2") (pintype "passive"))
      (node (ref "C30") (pin "1") (pinfunction "1_1") (pintype "passive"))
      (node (ref "C31") (pin "1") (pinfunction "1_1") (pintype "passive"))
      (node (ref "C32") (pin "2") (pinfunction "2_2") (pintype "passive"))
      (node (ref "C36") (pin "2") (pinfunction "2_2") (pintype "passive"))
      (node (ref "C37") (pin "1") (pinfunction "1_1") (pintype "passive"))
      (node (ref "C38") (pin "1") (pinfunction "1_1") (pintype "passive"))
      (node (ref "C39") (pin "1") (pinfunction "1_1") (pintype "passive"))
      (node (ref "C4") (pin "2") (pinfunction "2_2") (pintype "passive"))
      (node (ref "C40") (pin "1") (pinfunction "1_1") (pintype "passive"))
      (node (ref "C41") (pin "1") (pinfunction "1_1") (pintype "passive"))
      (node (ref "C42") (pin "1") (pinfunction "1_1") (pintype "passive"))
      (node (ref "C43") (pin "2") (pinfunction "2_2") (pintype "passive"))
      (node (ref "C44") (pin "2") (pinfunction "2_2") (pintype "passive"))
      (node (ref "C45") (pin "2") (pinfunction "2_2") (pintype "passive"))
      (node (ref "C46") (pin "2") (pinfunction "2_2") (pintype "passive"))
      (node (ref "C47") (pin "2") (pinfunction "2_2") (pintype "passive"))
      (node (ref "C48") (pin "2") (pinfunction "2_2") (pintype "passive"))
      (node (ref "C5") (pin "2") (pinfunction "2_2") (pintype "passive"))
      (node (ref "C6") (pin "2") (pinfunction "2_2") (pintype "passive"))
      (node (ref "C7") (pin "2") (pinfunction "2_2") (pintype "passive"))
      (node (ref "C8") (pin "2") (pinfunction "2_2") (pintype "passive"))
      (node (ref "C9") (pin "1") (pinfunction "1_1") (pintype "passive"))
      (node (ref "DA1") (pin "2") (pinfunction "GND_2") (pintype "power_in"))
      (node (ref "DD1") (pin "11") (pinfunction "AGNDVCO_11") (pintype "power_in"))
      (node (ref "DD1") (pin "18") (pinfunction "AGNDVCO_18") (pintype "power_in"))
      (node (ref "DD1") (pin "21") (pinfunction "AGNDVCO_21") (pintype "power_in"))
      (node (ref "DD1") (pin "27") (pinfunction "DGND_27") (pintype "power_in"))
      (node (ref "DD1") (pin "31") (pinfunction "SDGND_31") (pintype "power_in"))
      (node (ref "DD1") (pin "33") (pinfunction "EP_33") (pintype "power_in"))
      (node (ref "DD1") (pin "8") (pinfunction "CPGND_8") (pintype "power_in"))
      (node (ref "DD1") (pin "9") (pinfunction "AGND_9") (pintype "power_in"))
      (node (ref "DD2") (pin "5") (pinfunction "GND_5") (pintype "passive"))
      (node (ref "DD2") (pin "6") (pinfunction "GND_6") (pintype "passive"))
      (node (ref "DD3") (pin "2") (pinfunction "GND_2") (pintype "passive"))
      (node (ref "DD3") (pin "4") (pinfunction "GND_4") (pintype "passive"))
      (node (ref "DD4") (pin "17") (pinfunction "EP_17") (pintype "power_in"))
      (node (ref "DD5") (pin "1") (pinfunction "~{OE}_1") (pintype "input"))
      (node (ref "DD5") (pin "3") (pinfunction "GND_3") (pintype "power_in"))
      (node (ref "DD6") (pin "1") (pinfunction "~{OE}_1") (pintype "input"))
      (node (ref "DD6") (pin "3") (pinfunction "GND_3") (pintype "power_in"))
      (node (ref "DD7") (pin "4") (pinfunction "GND_4") (pintype "power_in"))
      (node (ref "DD8") (pin "1") (pinfunction "~{OE}_1") (pintype "input"))
      (node (ref "DD8") (pin "3") (pinfunction "GND_3") (pintype "power_in"))
      (node (ref "DD9") (pin "1") (pinfunction "~{OE}_1") (pintype "input"))
      (node (ref "DD9") (pin "3") (pinfunction "GND_3") (pintype "power_in"))
      (node (ref "LG1") (pin "2") (pinfunction "2_2") (pintype "passive"))
      (node (ref "LG1") (pin "4") (pinfunction "4_4") (pintype "passive"))
      (node (ref "LG1") (pin "6") (pinfunction "6_6") (pintype "passive"))
      (node (ref "LG1") (pin "8") (pinfunction "8_8") (pintype "passive"))
      (node (ref "R10") (pin "1") (pinfunction "1_1") (pintype "passive"))
      (node (ref "R11") (pin "1") (pinfunction "1_1") (pintype "passive"))
      (node (ref "R12") (pin "1") (pinfunction "1_1") (pintype "passive"))
      (node (ref "R15") (pin "1") (pinfunction "1_1") (pintype "passive"))
      (node (ref "R2") (pin "1") (pinfunction "1_1") (pintype "passive"))
      (node (ref "R5") (pin "2") (pinfunction "2_2") (pintype "passive"))
      (node (ref "R8") (pin "1") (pinfunction "1_1") (pintype "passive"))
      (node (ref "R9") (pin "2") (pinfunction "2_2") (pintype "passive"))
      (node (ref "U1") (pin "1") (pinfunction "GND_1") (pintype "power_in"))
      (node (ref "U2") (pin "5") (pinfunction "GND_5") (pintype "power_in"))
      (node (ref "XP2") (pin "MH") (pinfunction "MH_MH") (pintype "passive"))
      (node (ref "XP2") (pin "a16") (pinfunction "a16_a16") (pintype "passive"))
      (node (ref "XP2") (pin "a2") (pinfunction "a2_a2") (pintype "passive"))
      (node (ref "XP2") (pin "a4") (pinfunction "a4_a4") (pintype "passive"))
      (node (ref "XP2") (pin "a5") (pinfunction "a5_a5") (pintype "passive"))
      (node (ref "XP2") (pin "b2") (pinfunction "b2_b2") (pintype "passive"))
      (node (ref "XP2") (pin "b4") (pinfunction "b4_b4") (pintype "passive"))
      (node (ref "XP2") (pin "b5") (pinfunction "b5_b5") (pintype "passive"))
      (node (ref "XP2") (pin "c2") (pinfunction "c2_c2") (pintype "passive"))
      (node (ref "XP2") (pin "c4") (pinfunction "c4_c4") (pintype "passive"))
      (node (ref "XP2") (pin "c5") (pinfunction "c5_c5") (pintype "passive"))
      (node (ref "XW1") (pin "2") (pinfunction "2_2") (pintype "passive"))
      (node (ref "XW2") (pin "2") (pinfunction "2_2") (pintype "passive"))
      (node (ref "ZQ1") (pin "3") (pinfunction "Корпус_3") (pintype "passive"))
    )
    (net (code "25") (name "Net-(C18-Pad2)") (class "Default")
      (node (ref "C18") (pin "2") (pinfunction "2_2") (pintype "passive"))
      (node (ref "R4") (pin "1") (pinfunction "1_1") (pintype "passive"))
    )
    (net (code "26") (name "Net-(C26-Pad2)") (class "Default")
      (node (ref "C26") (pin "2") (pinfunction "2_2") (pintype "passive"))
      (node (ref "R7") (pin "1") (pinfunction "1_1") (pintype "passive"))
      (node (ref "R8") (pin "2") (pinfunction "2_2") (pintype "passive"))
    )
    (net (code "27") (name "Net-(C27-Pad1)") (class "Default")
      (node (ref "C27") (pin "1") (pinfunction "1_1") (pintype "passive"))
      (node (ref "C28") (pin "1") (pinfunction "1_1") (pintype "passive"))
      (node (ref "L2") (pin "2") (pinfunction "2_2") (pintype "passive"))
      (node (ref "R6") (pin "1") (pinfunction "1_1") (pintype "passive"))
    )
    (net (code "28") (name "Net-(DD1-CPOUT)") (class "Default")
      (node (ref "C18") (pin "1") (pinfunction "1_1") (pintype "passive"))
      (node (ref "DD1") (pin "7") (pinfunction "CPOUT_7") (pintype "output"))
      (node (ref "R3") (pin "1") (pinfunction "1_1") (pintype "passive"))
    )
    (net (code "29") (name "Net-(DD1-REFIN)") (class "Default")
      (node (ref "C1") (pin "2") (pinfunction "2_2") (pintype "passive"))
      (node (ref "DD1") (pin "29") (pinfunction "REFIN_29") (pintype "input"))
    )
    (net (code "30") (name "Net-(DD1-RSET)") (class "Default")
      (node (ref "DD1") (pin "22") (pinfunction "RSET_22") (pintype "passive"))
      (node (ref "R2") (pin "2") (pinfunction "2_2") (pintype "passive"))
    )
    (net (code "31") (name "Net-(DD1-SW)") (class "Default")
      (node (ref "DD1") (pin "5") (pinfunction "SW_5") (pintype "passive"))
      (node (ref "R1") (pin "2") (pinfunction "2_2") (pintype "passive"))
    )
    (net (code "32") (name "Net-(DD1-TEMP)") (class "Default")
      (node (ref "C2") (pin "1") (pinfunction "1_1") (pintype "passive"))
      (node (ref "C3") (pin "1") (pinfunction "1_1") (pintype "passive"))
      (node (ref "DD1") (pin "19") (pinfunction "TEMP_19") (pintype "output"))
    )
    (net (code "33") (name "Net-(DD1-VCOM)") (class "Default")
      (node (ref "C4") (pin "1") (pinfunction "1_1") (pintype "passive"))
      (node (ref "C5") (pin "1") (pinfunction "1_1") (pintype "passive"))
      (node (ref "DD1") (pin "23") (pinfunction "VCOM_23") (pintype "passive"))
    )
    (net (code "34") (name "Net-(DD1-VREF)") (class "Default")
      (node (ref "C6") (pin "1") (pinfunction "1_1") (pintype "passive"))
      (node (ref "C7") (pin "1") (pinfunction "1_1") (pintype "passive"))
      (node (ref "DD1") (pin "24") (pinfunction "VREF_24") (pintype "passive"))
    )
    (net (code "35") (name "Net-(DD1-VTUNE)") (class "Default")
      (node (ref "C19") (pin "2") (pinfunction "2_2") (pintype "passive"))
      (node (ref "DD1") (pin "20") (pinfunction "VTUNE_20") (pintype "input"))
      (node (ref "R3") (pin "2") (pinfunction "2_2") (pintype "passive"))
    )
    (net (code "36") (name "Net-(DD2-GND{slash}DC_Feed_+RF_GND)") (class "Default")
      (node (ref "DD2") (pin "2") (pinfunction "GND/DC_Feed_+RF_GND_2") (pintype "passive"))
      (node (ref "L1") (pin "1") (pinfunction "1_1") (pintype "passive"))
    )
    (net (code "37") (name "Net-(DD2-Unbalanced)") (class "Default")
      (node (ref "C25") (pin "1") (pinfunction "1_1") (pintype "passive"))
      (node (ref "DD2") (pin "1") (pinfunction "Unbalanced_1") (pintype "passive"))
    )
    (net (code "38") (name "Net-(DD3A-RF_In)") (class "Default")
      (node (ref "C25") (pin "2") (pinfunction "2_2") (pintype "passive"))
      (node (ref "DD3") (pin "1") (pinfunction "RF_In_1") (pintype "input"))
    )
    (net (code "39") (name "Net-(DD3A-RF_Out)") (class "Default")
      (node (ref "C26") (pin "1") (pinfunction "1_1") (pintype "passive"))
      (node (ref "DD3") (pin "3") (pinfunction "RF_Out_3") (pintype "output"))
      (node (ref "L2") (pin "1") (pinfunction "1_1") (pintype "passive"))
    )
    (net (code "40") (name "Net-(DD4-BGAP_DECAP)") (class "Default")
      (node (ref "C36") (pin "1") (pinfunction "1_1") (pintype "passive"))
      (node (ref "DD4") (pin "15") (pinfunction "BGAP_DECAP_15") (pintype "passive"))
    )
    (net (code "41") (name "Net-(DD4-CHIP0)") (class "Default")
      (node (ref "DD4") (pin "1") (pinfunction "CHIP0_1") (pintype "passive"))
      (node (ref "R10") (pin "2") (pinfunction "2_2") (pintype "passive"))
    )
    (net (code "42") (name "Net-(DD4-CHIP1)") (class "Default")
      (node (ref "DD4") (pin "4") (pinfunction "CHIP1_4") (pintype "passive"))
      (node (ref "R11") (pin "2") (pinfunction "2_2") (pintype "passive"))
    )
    (net (code "43") (name "Net-(DD4-CHIP2)") (class "Default")
      (node (ref "DD4") (pin "5") (pinfunction "CHIP2_5") (pintype "passive"))
      (node (ref "R12") (pin "2") (pinfunction "2_2") (pintype "passive"))
    )
    (net (code "44") (name "Net-(DD4-FB_DECAP)") (class "Default")
      (node (ref "C35") (pin "2") (pinfunction "2_2") (pintype "passive"))
      (node (ref "DD4") (pin "14") (pinfunction "FB_DECAP_14") (pintype "power_in"))
    )
    (net (code "45") (name "Net-(DD4-TRIG)") (class "Default")
      (node (ref "DD4") (pin "13") (pinfunction "TRIG_13") (pintype "passive"))
      (node (ref "R13") (pin "1") (pinfunction "1_1") (pintype "passive"))
      (node (ref "R14") (pin "1") (pinfunction "1_1") (pintype "passive"))
      (node (ref "R15") (pin "2") (pinfunction "2_2") (pintype "passive"))
    )
    (net (code "46") (name "Net-(DD4-VDD3_DECAP)") (class "Default")
      (node (ref "C35") (pin "1") (pinfunction "1_1") (pintype "passive"))
      (node (ref "C39") (pin "2") (pinfunction "2_2") (pintype "passive"))
      (node (ref "C40") (pin "2") (pinfunction "2_2") (pintype "passive"))
      (node (ref "DD4") (pin "12") (pinfunction "VDD3_DECAP_12") (pintype "passive"))
    )
    (net (code "47") (name "Net-(DD5A-A)") (class "Default")
      (node (ref "DD5") (pin "2") (pinfunction "A_2") (pintype "input"))
      (node (ref "U2") (pin "7") (pinfunction "Q_7") (pintype "output"))
    )
    (net (code "48") (name "Net-(DD5A-Y)") (class "Default")
      (node (ref "DD5") (pin "4") (pinfunction "Y_4") (pintype "output"))
      (node (ref "DD6") (pin "2") (pinfunction "A_2") (pintype "input"))
    )
    (net (code "49") (name "Net-(DD6A-Y)") (class "Default")
      (node (ref "DD6") (pin "4") (pinfunction "Y_4") (pintype "output"))
      (node (ref "DD7") (pin "1") (pinfunction "CP_1") (pintype "passive"))
    )
    (net (code "50") (name "Net-(DD7-D)") (class "Default")
      (node (ref "DD7") (pin "2") (pinfunction "D_2") (pintype "passive"))
      (node (ref "DD7") (pin "3") (pinfunction "~{Q}_3") (pintype "passive"))
    )
    (net (code "51") (name "Net-(DD7-Q)") (class "Default")
      (node (ref "DD7") (pin "5") (pinfunction "Q_5") (pintype "passive"))
      (node (ref "DD8") (pin "2") (pinfunction "A_2") (pintype "input"))
      (node (ref "DD9") (pin "2") (pinfunction "A_2") (pintype "input"))
    )
    (net (code "52") (name "Net-(DD8A-Y)") (class "Default")
      (node (ref "DD8") (pin "4") (pinfunction "Y_4") (pintype "output"))
      (node (ref "R16") (pin "2") (pinfunction "2_2") (pintype "passive"))
      (node (ref "XW2") (pin "1") (pinfunction "1_1") (pintype "passive"))
    )
    (net (code "53") (name "Net-(DD9A-Y)") (class "Default")
      (node (ref "DD9") (pin "4") (pinfunction "Y_4") (pintype "output"))
      (node (ref "R16") (pin "1") (pinfunction "1_1") (pintype "passive"))
    )
    (net (code "54") (name "Net-(LG1-Pad1)") (class "Default")
      (node (ref "LG1") (pin "1") (pinfunction "1_1") (pintype "passive"))
      (node (ref "R17") (pin "1") (pinfunction "1_1") (pintype "passive"))
    )
    (net (code "55") (name "Net-(LG1-Pad3)") (class "Default")
      (node (ref "LG1") (pin "3") (pinfunction "3_3") (pintype "passive"))
      (node (ref "R18") (pin "1") (pinfunction "1_1") (pintype "passive"))
    )
    (net (code "56") (name "Net-(LG1-Pad5)") (class "Default")
      (node (ref "LG1") (pin "5") (pinfunction "5_5") (pintype "passive"))
      (node (ref "R19") (pin "1") (pinfunction "1_1") (pintype "passive"))
    )
    (net (code "57") (name "Net-(LG1-Pad7)") (class "Default")
      (node (ref "LG1") (pin "7") (pinfunction "7_7") (pintype "passive"))
      (node (ref "R20") (pin "1") (pinfunction "1_1") (pintype "passive"))
    )
    (net (code "58") (name "Net-(R7-Pad2)") (class "Default")
      (node (ref "R7") (pin "2") (pinfunction "2_2") (pintype "passive"))
      (node (ref "R9") (pin "1") (pinfunction "1_1") (pintype "passive"))
      (node (ref "XW1") (pin "1") (pinfunction "1_1") (pintype "passive"))
    )
    (net (code "59") (name "unconnected-(U2-NC-Pad1)") (class "Default")
      (node (ref "U2") (pin "1") (pinfunction "NC_1") (pintype "passive+no_connect"))
    )
    (net (code "60") (name "unconnected-(U2-NC-Pad6)") (class "Default")
      (node (ref "U2") (pin "6") (pinfunction "NC_6") (pintype "passive+no_connect"))
    )
    (net (code "61") (name "unconnected-(U2-VBB-Pad4)") (class "Default")
      (node (ref "U2") (pin "4") (pinfunction "VBB_4") (pintype "output+no_connect"))
    )
    (net (code "62") (name "unconnected-(XP2-Pada3)") (class "Default")
      (node (ref "XP2") (pin "a3") (pinfunction "a3_a3") (pintype "passive"))
    )
    (net (code "63") (name "unconnected-(XP2-Pada6)") (class "Default")
      (node (ref "XP2") (pin "a6") (pinfunction "a6_a6") (pintype "passive"))
    )
    (net (code "64") (name "unconnected-(XP2-Pada7)") (class "Default")
      (node (ref "XP2") (pin "a7") (pinfunction "a7_a7") (pintype "passive"))
    )
    (net (code "65") (name "unconnected-(XP2-Pada8)") (class "Default")
      (node (ref "XP2") (pin "a8") (pinfunction "a8_a8") (pintype "passive"))
    )
    (net (code "66") (name "unconnected-(XP2-Pada9)") (class "Default")
      (node (ref "XP2") (pin "a9") (pinfunction "a9_a9") (pintype "passive"))
    )
    (net (code "67") (name "unconnected-(XP2-Padb3)") (class "Default")
      (node (ref "XP2") (pin "b3") (pinfunction "b3_b3") (pintype "passive"))
    )
    (net (code "68") (name "unconnected-(XP2-Padb6)") (class "Default")
      (node (ref "XP2") (pin "b6") (pinfunction "b6_b6") (pintype "passive"))
    )
    (net (code "69") (name "unconnected-(XP2-Padb7)") (class "Default")
      (node (ref "XP2") (pin "b7") (pinfunction "b7_b7") (pintype "passive"))
    )
    (net (code "70") (name "unconnected-(XP2-Padb8)") (class "Default")
      (node (ref "XP2") (pin "b8") (pinfunction "b8_b8") (pintype "passive"))
    )
    (net (code "71") (name "unconnected-(XP2-Padb9)") (class "Default")
      (node (ref "XP2") (pin "b9") (pinfunction "b9_b9") (pintype "passive"))
    )
    (net (code "72") (name "unconnected-(XP2-Padb10)") (class "Default")
      (node (ref "XP2") (pin "b10") (pinfunction "b10_b10") (pintype "passive"))
    )
    (net (code "73") (name "unconnected-(XP2-Padb11)") (class "Default")
      (node (ref "XP2") (pin "b11") (pinfunction "b11_b11") (pintype "passive"))
    )
    (net (code "74") (name "unconnected-(XP2-Padb12)") (class "Default")
      (node (ref "XP2") (pin "b12") (pinfunction "b12_b12") (pintype "passive"))
    )
    (net (code "75") (name "unconnected-(XP2-Padb13)") (class "Default")
      (node (ref "XP2") (pin "b13") (pinfunction "b13_b13") (pintype "passive"))
    )
    (net (code "76") (name "unconnected-(XP2-Padb14)") (class "Default")
      (node (ref "XP2") (pin "b14") (pinfunction "b14_b14") (pintype "passive"))
    )
    (net (code "77") (name "unconnected-(XP2-Padb15)") (class "Default")
      (node (ref "XP2") (pin "b15") (pinfunction "b15_b15") (pintype "passive"))
    )
    (net (code "78") (name "unconnected-(XP2-Padc3)") (class "Default")
      (node (ref "XP2") (pin "c3") (pinfunction "c3_c3") (pintype "passive"))
    )
    (net (code "79") (name "unconnected-(XP2-Padc7)") (class "Default")
      (node (ref "XP2") (pin "c7") (pinfunction "c7_c7") (pintype "passive"))
    )
    (net (code "80") (name "unconnected-(XP2-Padc9)") (class "Default")
      (node (ref "XP2") (pin "c9") (pinfunction "c9_c9") (pintype "passive"))
    )
    (net (code "81") (name "unconnected-(XP2-Padc11)") (class "Default")
      (node (ref "XP2") (pin "c11") (pinfunction "c11_c11") (pintype "passive"))
    )
    (net (code "82") (name "unconnected-(XP2-Padc12)") (class "Default")
      (node (ref "XP2") (pin "c12") (pinfunction "c12_c12") (pintype "passive"))
    )
    (net (code "83") (name "unconnected-(XP2-Padc13)") (class "Default")
      (node (ref "XP2") (pin "c13") (pinfunction "c13_c13") (pintype "passive"))
    )
    (net (code "84") (name "unconnected-(XP2-Padc14)") (class "Default")
      (node (ref "XP2") (pin "c14") (pinfunction "c14_c14") (pintype "passive"))
    )
    (net (code "85") (name "unconnected-(XP2-Padc15)") (class "Default")
      (node (ref "XP2") (pin "c15") (pinfunction "c15_c15") (pintype "passive"))
    )
    (net (code "86") (name "unconnected-(XP2-Padc16)") (class "Default")
      (node (ref "XP2") (pin "c16") (pinfunction "c16_c16") (pintype "passive"))
    )
    (net (code "87") (name "unconnected-(ZQ1-N.C.-Pad1)") (class "Default")
      (node (ref "ZQ1") (pin "1") (pinfunction "N.C._1") (pintype "passive+no_connect"))
    )
    (net (code "88") (name "unconnected-(ZQ1-N.C.-Pad5)") (class "Default")
      (node (ref "ZQ1") (pin "5") (pinfunction "N.C._5") (pintype "passive+no_connect"))
    )
  )
)
